# EEG_cap_v2.net
KiCad netlist of a schematic drawn in EAGLE
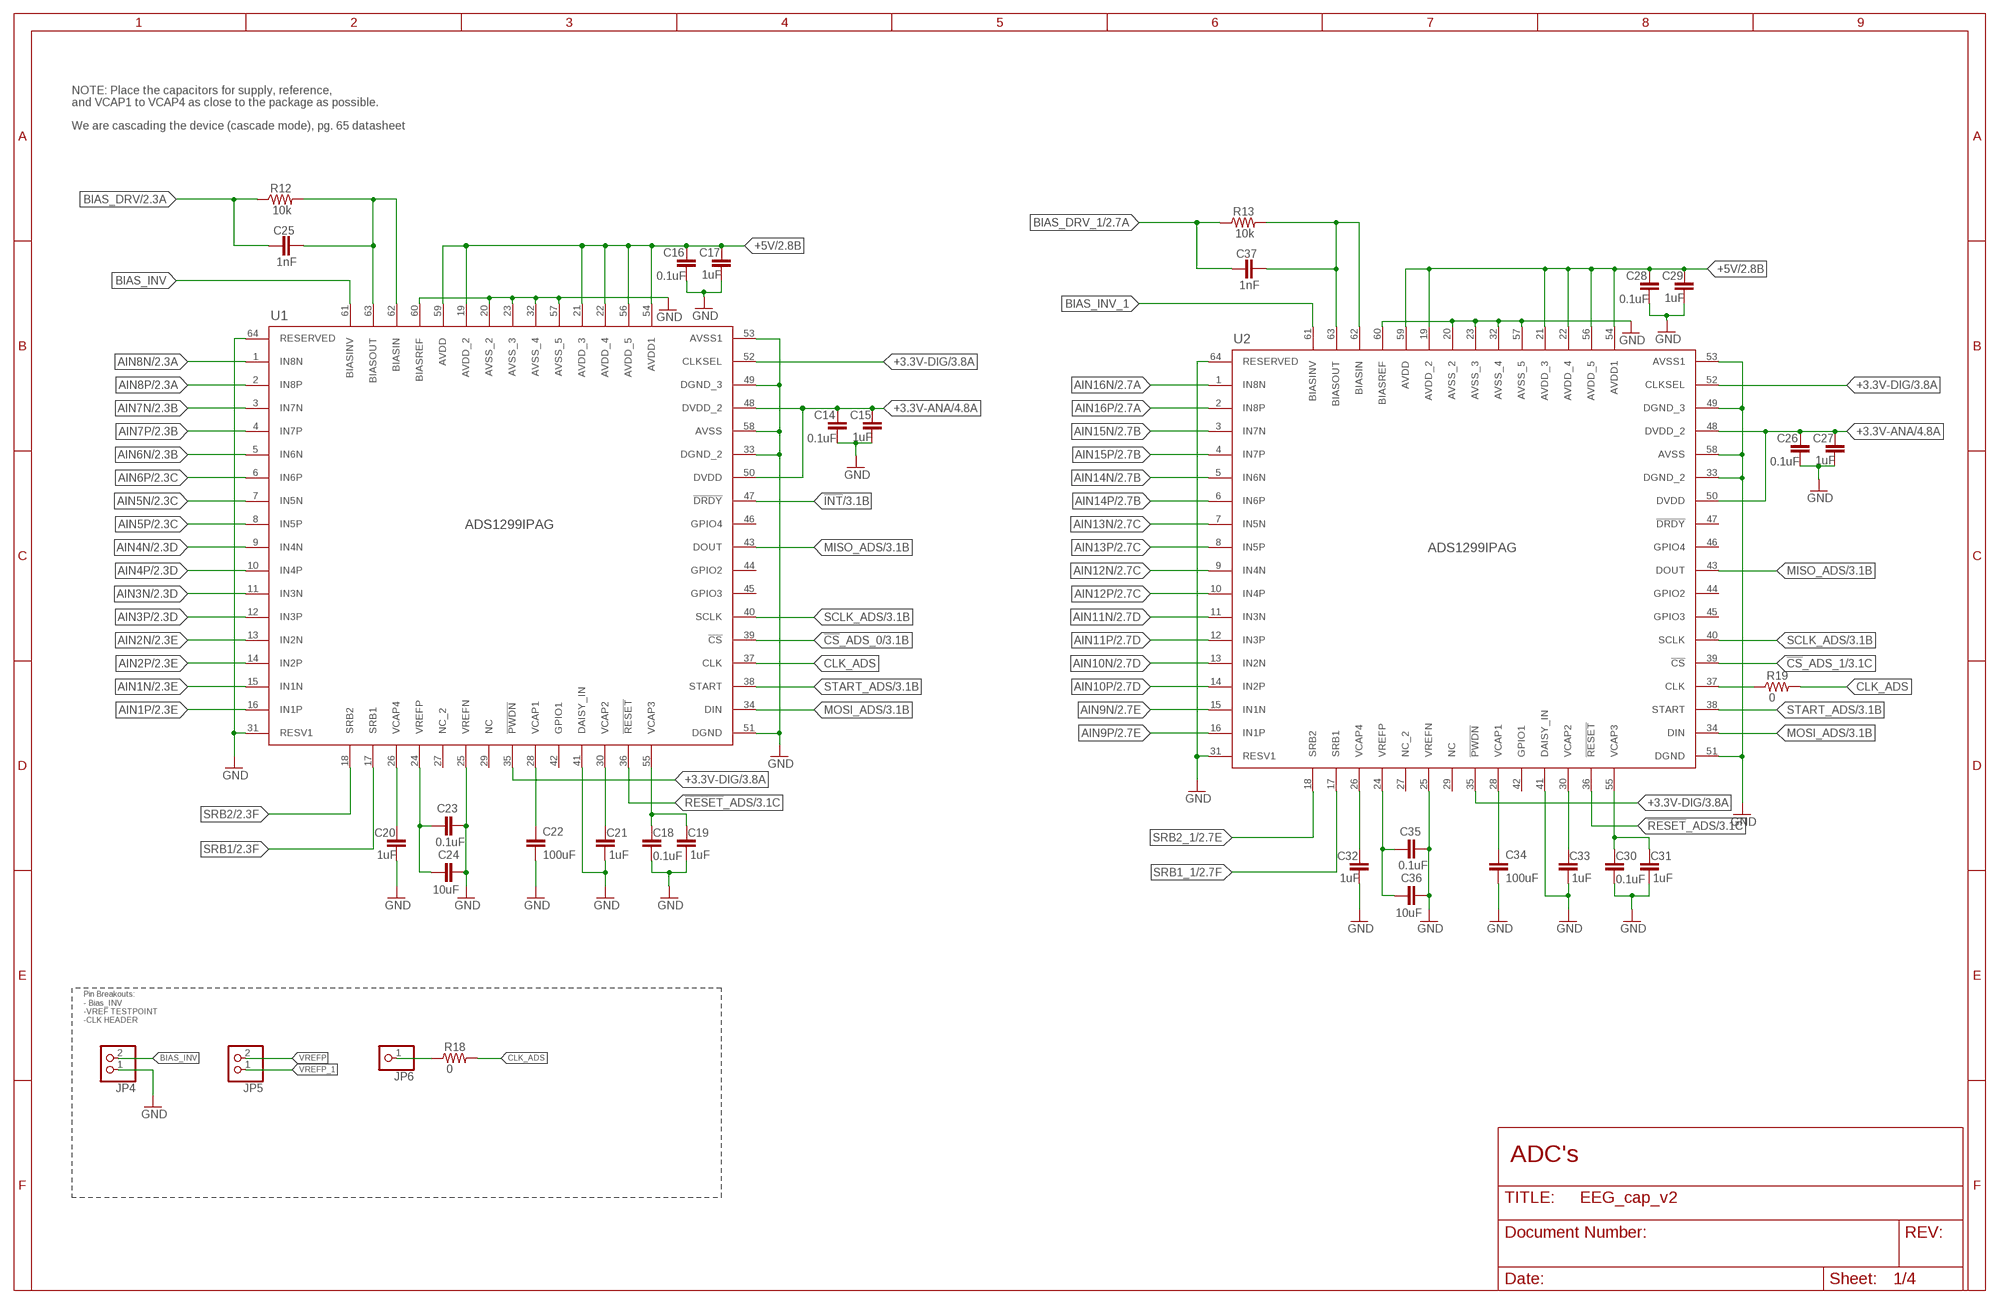
[diagram p0: schematic, sheet 1]
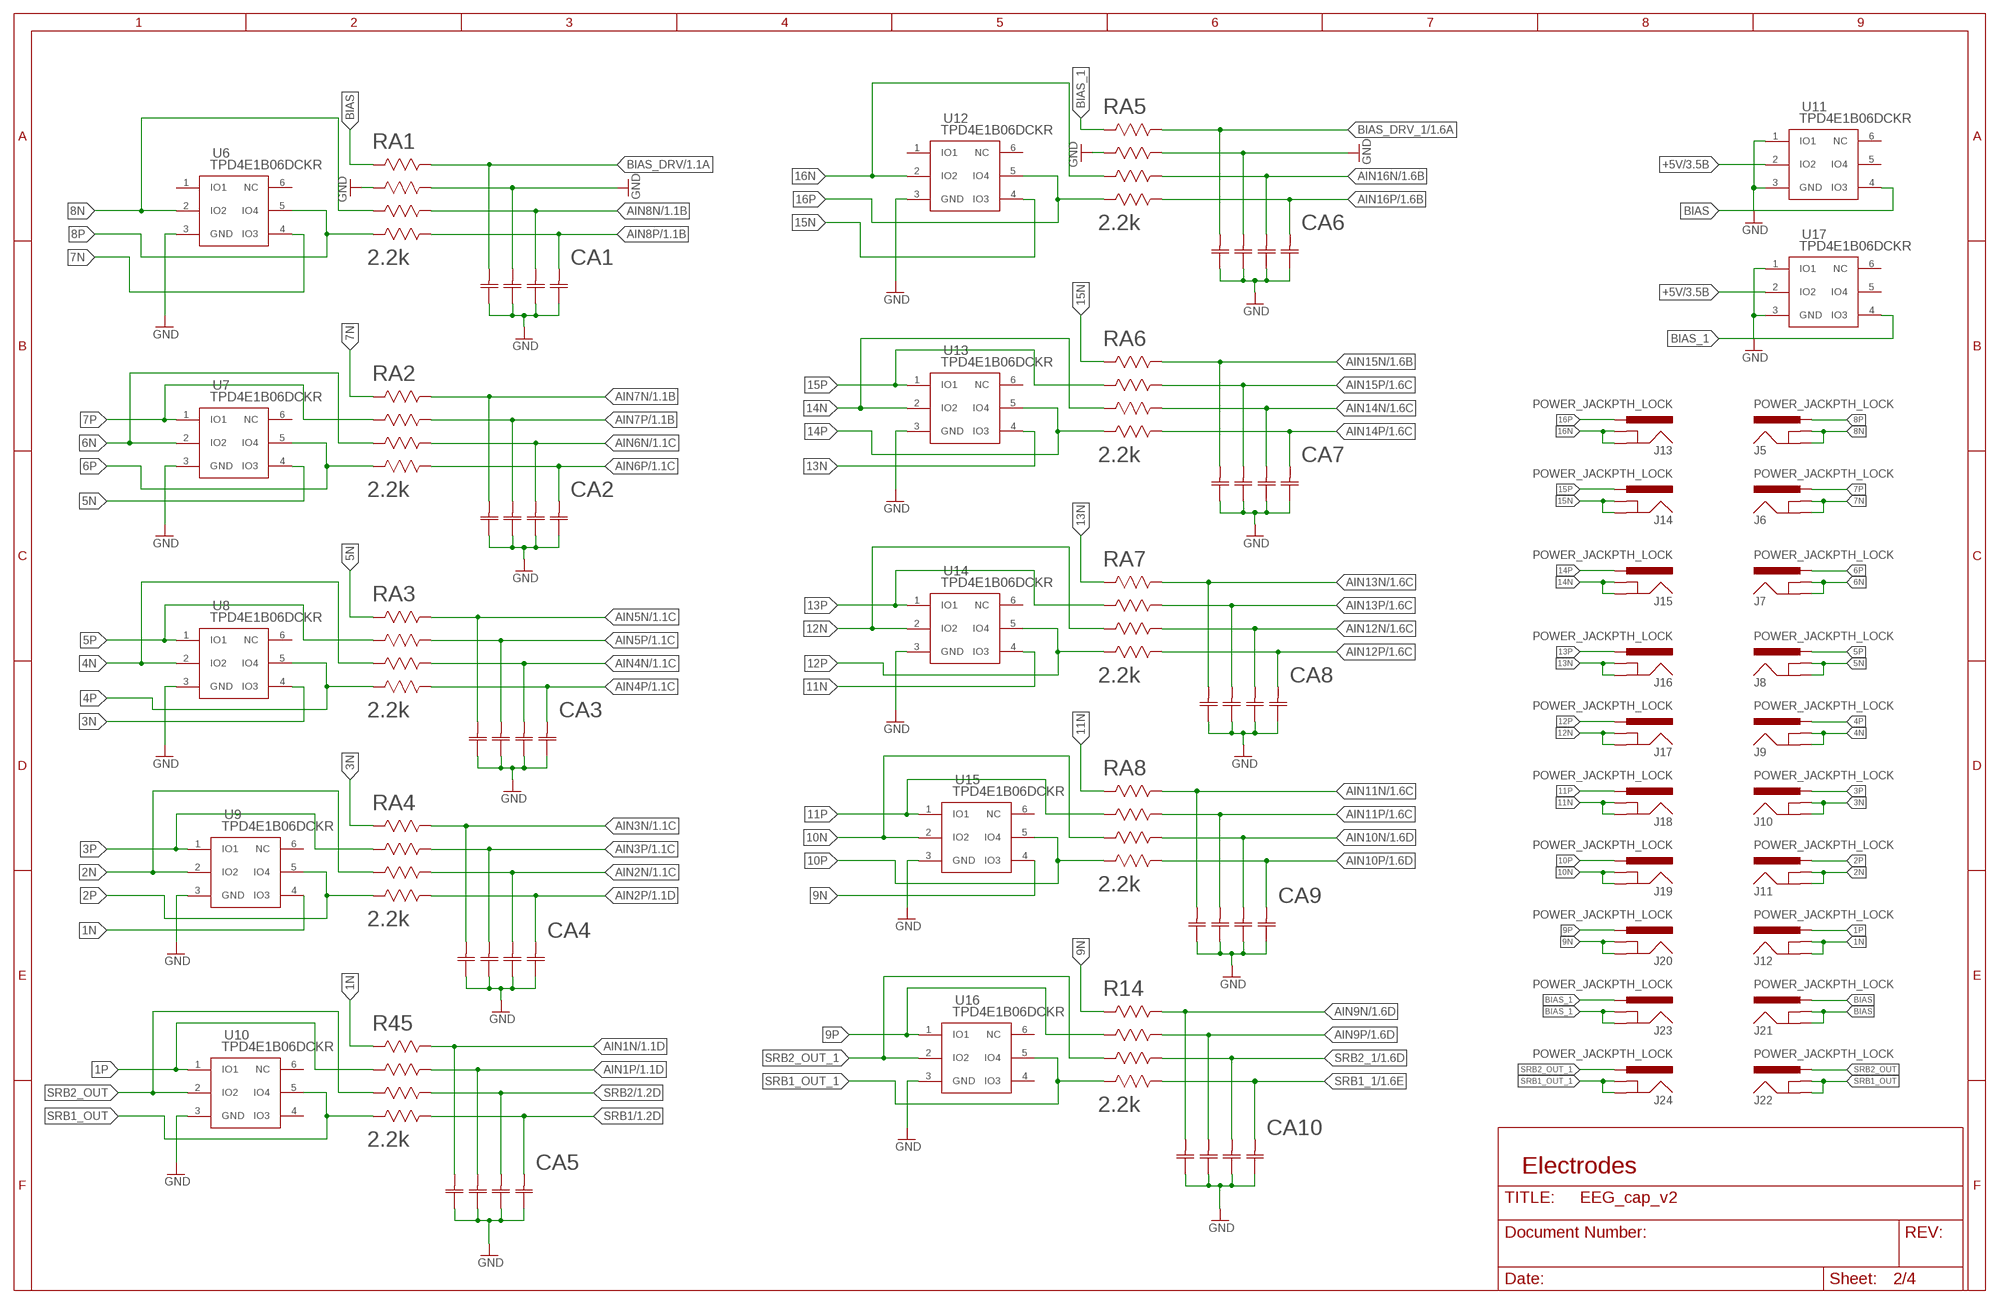
[diagram p1: schematic, sheet 2]
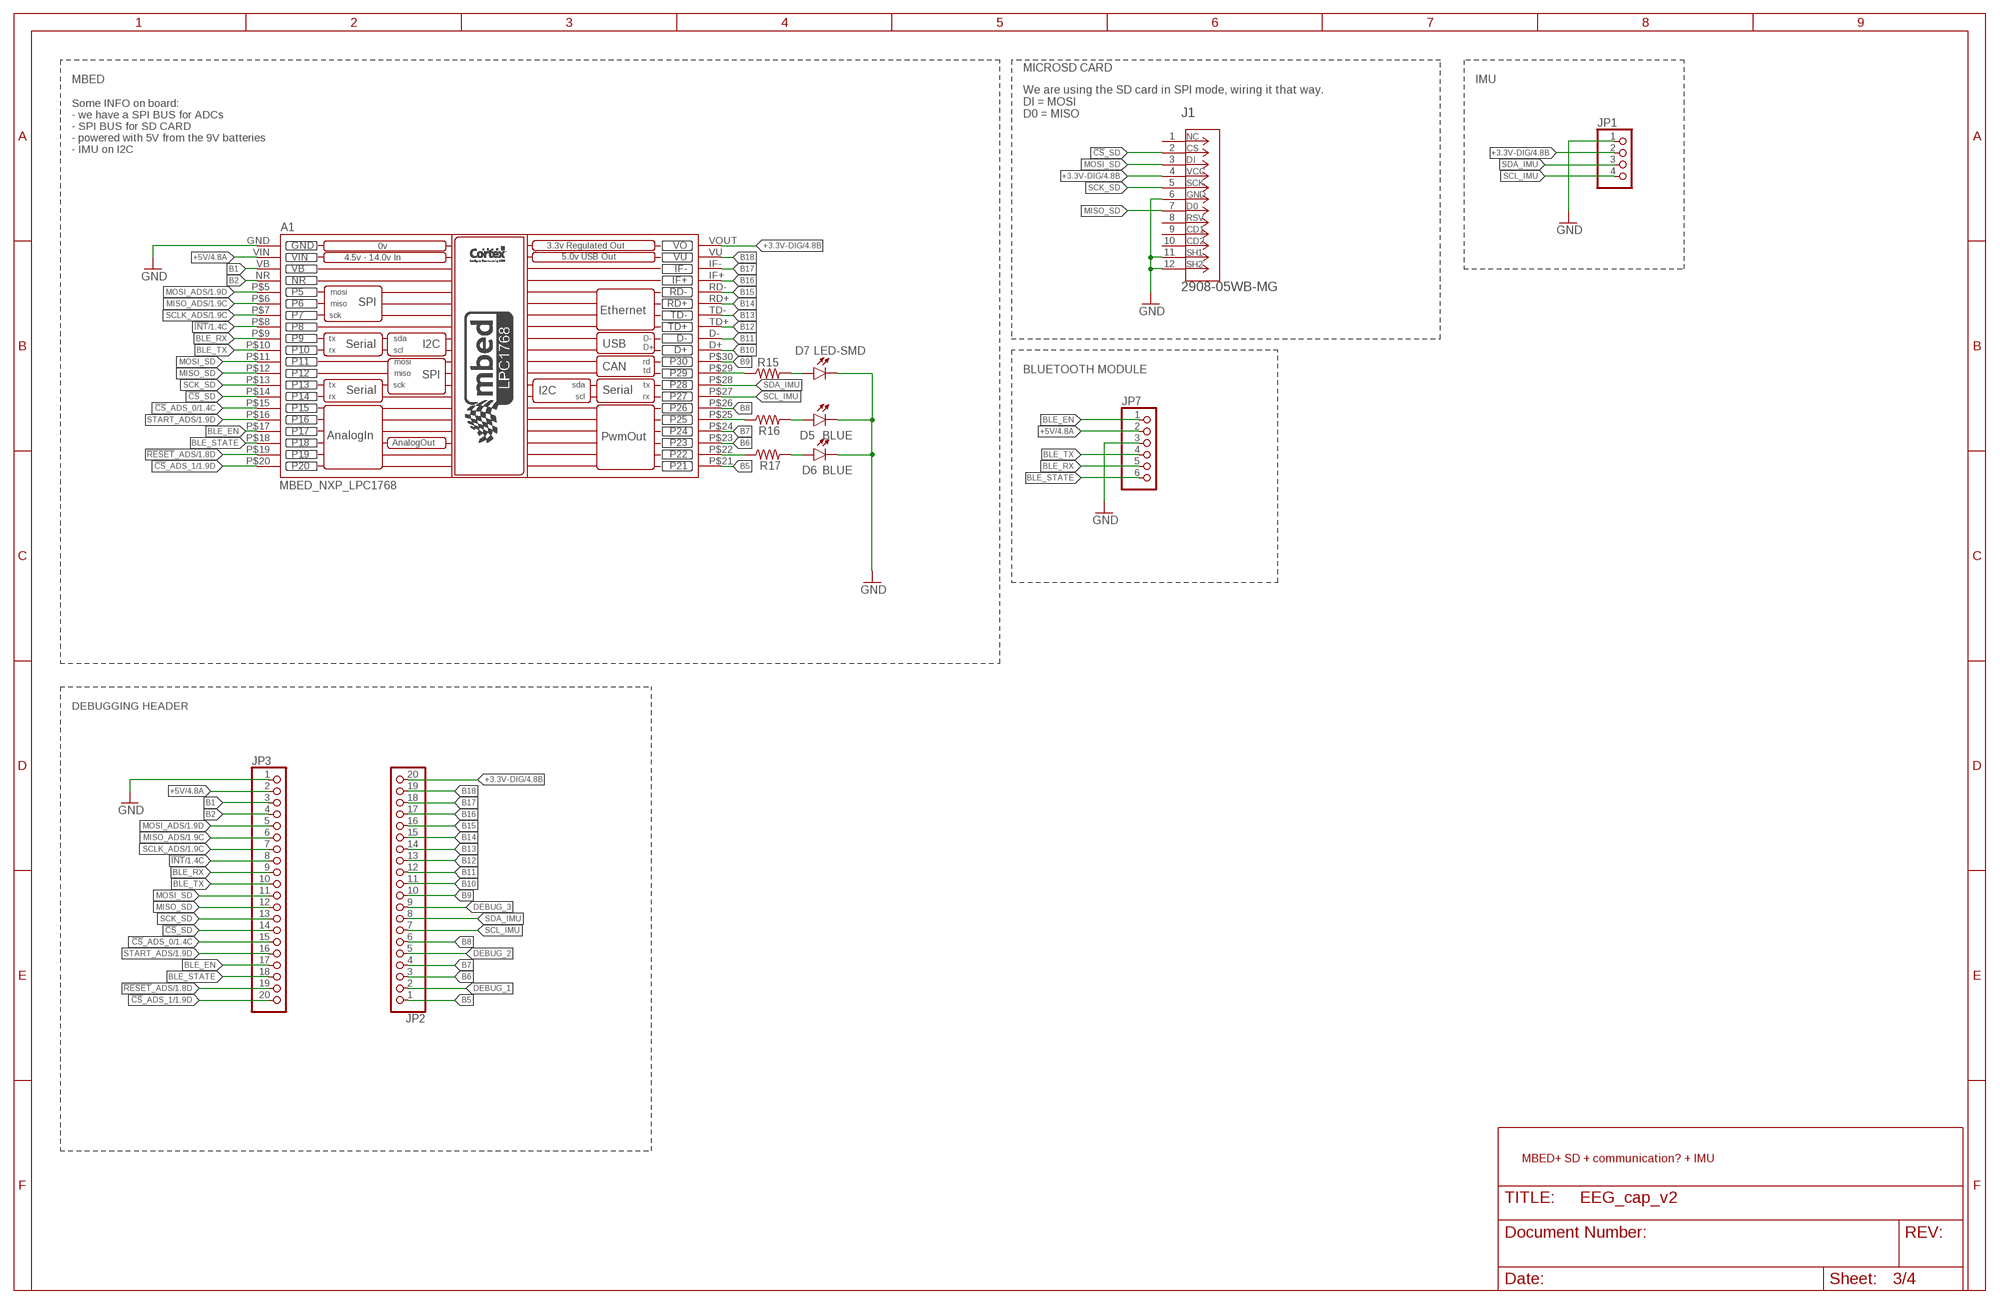
[diagram p2: schematic, sheet 3]
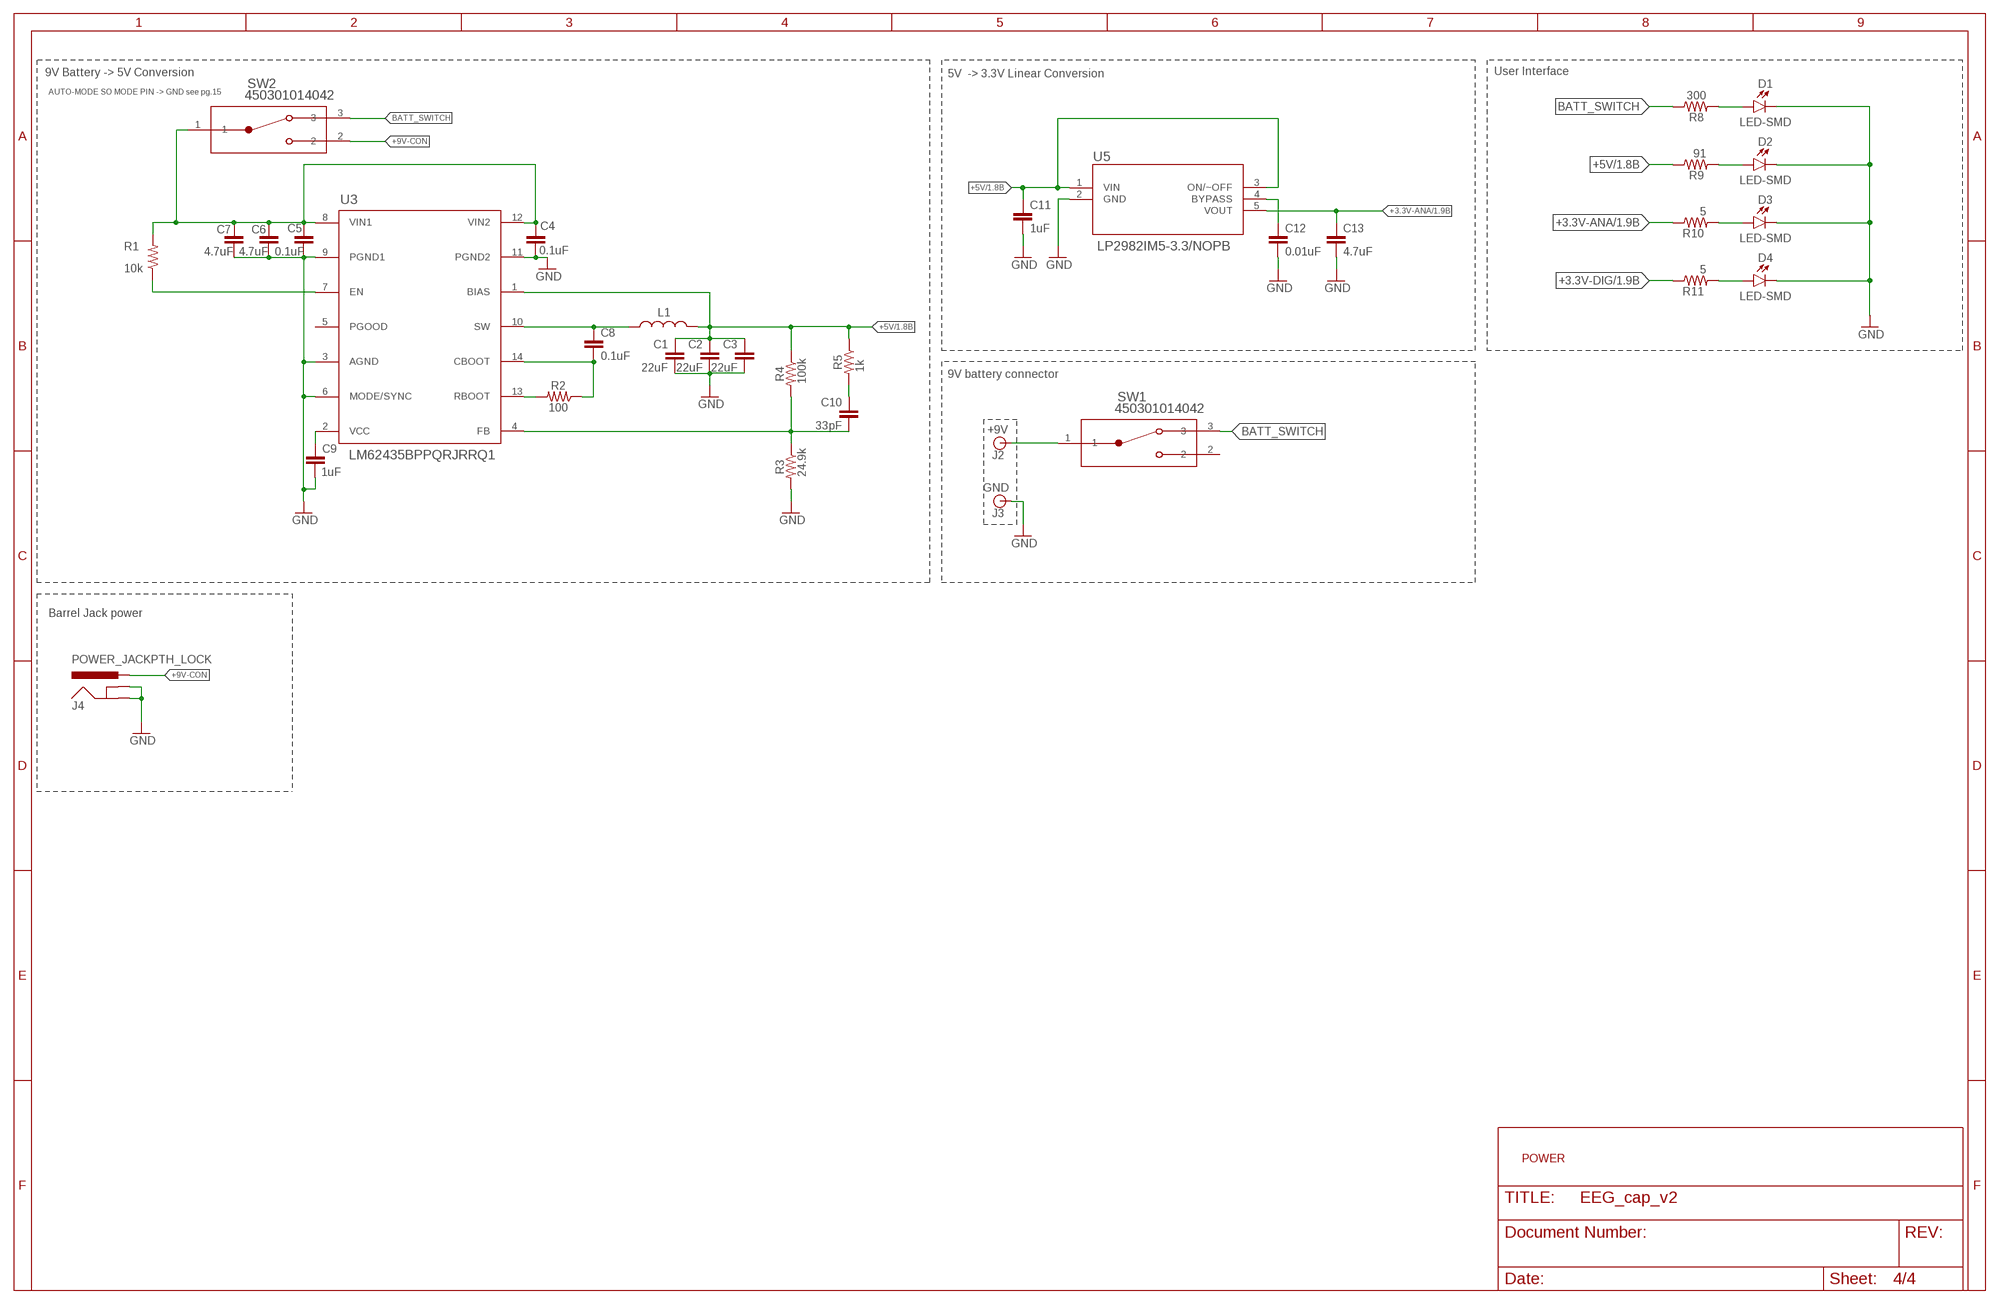
[diagram p3: schematic, sheet 4]

(export (version "E")
  (design (tool "Eeschema 10.0.6"))
  (components
    (comp (ref "C1")
      (value "22uF")
      (footprint "eagle-import:C0805")
      (libsource (lib "eagle-import") (part "C-EUC0805"))
    )
    (comp (ref "C2")
      (value "22uF")
      (footprint "eagle-import:C0805")
      (libsource (lib "eagle-import") (part "C-EUC0805"))
    )
    (comp (ref "C3")
      (value "22uF")
      (footprint "eagle-import:C0805")
      (libsource (lib "eagle-import") (part "C-EUC0805"))
    )
    (comp (ref "C4")
      (value "0.1uF")
      (footprint "eagle-import:C0805")
      (libsource (lib "eagle-import") (part "C-EUC0805"))
    )
    (comp (ref "C5")
      (value "0.1uF")
      (footprint "eagle-import:C0805")
      (libsource (lib "eagle-import") (part "C-EUC0805"))
    )
    (comp (ref "C6")
      (value "4.7uF")
      (footprint "eagle-import:C0805")
      (libsource (lib "eagle-import") (part "C-EUC0805"))
    )
    (comp (ref "C7")
      (value "4.7uF")
      (footprint "eagle-import:C0805")
      (libsource (lib "eagle-import") (part "C-EUC0805"))
    )
    (comp (ref "C8")
      (value "0.1uF")
      (footprint "eagle-import:C0805")
      (libsource (lib "eagle-import") (part "C-EUC0805"))
    )
    (comp (ref "C9")
      (value "1uF")
      (footprint "eagle-import:C0805")
      (libsource (lib "eagle-import") (part "C-EUC0805"))
    )
    (comp (ref "C10")
      (value "33pF")
      (footprint "eagle-import:C0805")
      (libsource (lib "eagle-import") (part "C-EUC0805"))
    )
    (comp (ref "C11")
      (value "1uF")
      (footprint "eagle-import:C0805")
      (libsource (lib "eagle-import") (part "C-EUC0805"))
    )
    (comp (ref "C12")
      (value "0.01uF")
      (footprint "eagle-import:C0805")
      (libsource (lib "eagle-import") (part "C-EUC0805"))
    )
    (comp (ref "C13")
      (value "4.7uF")
      (footprint "eagle-import:C0805")
      (libsource (lib "eagle-import") (part "C-EUC0805"))
    )
    (comp (ref "D1")
      (value "LED-SMD")
      (footprint "eagle-import:LED0603")
      (libsource (lib "eagle-import") (part "LED-SMD"))
    )
    (comp (ref "D2")
      (value "LED-SMD")
      (footprint "eagle-import:LED0603")
      (libsource (lib "eagle-import") (part "LED-SMD"))
    )
    (comp (ref "D3")
      (value "LED-SMD")
      (footprint "eagle-import:LED0603")
      (libsource (lib "eagle-import") (part "LED-SMD"))
    )
    (comp (ref "D4")
      (value "LED-SMD")
      (footprint "eagle-import:LED0603")
      (libsource (lib "eagle-import") (part "LED-SMD"))
    )
    (comp (ref "J2")
      (value "+9V")
      (footprint "eagle-import:BANANA_CONN")
      (libsource (lib "eagle-import") (part "BANANA_CONN"))
    )
    (comp (ref "J3")
      (value "GND")
      (footprint "eagle-import:BANANA_CONN")
      (libsource (lib "eagle-import") (part "BANANA_CONN"))
    )
    (comp (ref "J4")
      (value "POWER_JACKPTH_LOCK")
      (footprint "eagle-import:POWER_JACK_PTH_LOCK")
      (libsource (lib "eagle-import") (part "POWER_JACKPTH_LOCK"))
    )
    (comp (ref "L1")
      (value "DFE252010P-1R5M=P2")
      (footprint "eagle-import:INDC2520X100N")
      (fields (field (name "DIGI-KEY_PART_NUMBER") "490-10636-1-ND") (field (name "MF") "Murata"))
      (libsource (lib "eagle-import") (part "DFE252010P-1R5M=P2"))
    )
    (comp (ref "R1")
      (value "10k")
      (footprint "eagle-import:R0805")
      (libsource (lib "eagle-import") (part "R-US_R0805"))
    )
    (comp (ref "R2")
      (value "100")
      (footprint "eagle-import:R0805")
      (libsource (lib "eagle-import") (part "R-US_R0805"))
    )
    (comp (ref "R3")
      (value "24.9k")
      (footprint "eagle-import:R0805")
      (libsource (lib "eagle-import") (part "R-US_R0805"))
    )
    (comp (ref "R4")
      (value "100k")
      (footprint "eagle-import:R0805")
      (libsource (lib "eagle-import") (part "R-US_R0805"))
    )
    (comp (ref "R5")
      (value "1k")
      (footprint "eagle-import:R0805")
      (libsource (lib "eagle-import") (part "R-US_R0805"))
    )
    (comp (ref "R8")
      (value "300")
      (footprint "eagle-import:R0805")
      (libsource (lib "eagle-import") (part "R-US_R0805"))
    )
    (comp (ref "R9")
      (value "91")
      (footprint "eagle-import:R0805")
      (libsource (lib "eagle-import") (part "R-US_R0805"))
    )
    (comp (ref "R10")
      (value "5")
      (footprint "eagle-import:R0805")
      (libsource (lib "eagle-import") (part "R-US_R0805"))
    )
    (comp (ref "R11")
      (value "5")
      (footprint "eagle-import:R0805")
      (libsource (lib "eagle-import") (part "R-US_R0805"))
    )
    (comp (ref "SW1")
      (value "450301014042")
      (footprint "eagle-import:SW_450301014042_WRE")
      (fields (field (name "COPYRIGHT") "Copyright (C) 2021 Ultra Librarian. All rights reserved."))
      (libsource (lib "eagle-import") (part "450301014042"))
    )
    (comp (ref "SW2")
      (value "450301014042")
      (footprint "eagle-import:SW_450301014042_WRE")
      (fields (field (name "COPYRIGHT") "Copyright (C) 2021 Ultra Librarian. All rights reserved."))
      (libsource (lib "eagle-import") (part "450301014042"))
    )
    (comp (ref "U3")
      (value "LM62435BPPQRJRRQ1")
      (footprint "eagle-import:VQFN-HR14_RJR_TEX")
      (fields (field (name "COPYRIGHT") "Copyright (C) 2021 Ultra Librarian. All rights reserved."))
      (libsource (lib "eagle-import") (part "LM62435BPPQRJRRQ1"))
    )
    (comp (ref "U5")
      (value "LP2982IM5-3.3/NOPB")
      (footprint "eagle-import:MF05A")
      (fields (field (name "COPYRIGHT") "Copyright (C) 2021 Ultra Librarian. All rights reserved."))
      (libsource (lib "eagle-import") (part "LP2982IM5-3.3/NOPB"))
    )
    (comp (ref "C14")
      (value "0.1uF")
      (footprint "eagle-import:C0603")
      (libsource (lib "eagle-import") (part "C-EUC0603"))
    )
    (comp (ref "C15")
      (value "1uF")
      (footprint "eagle-import:C0603")
      (libsource (lib "eagle-import") (part "C-EUC0603"))
    )
    (comp (ref "C16")
      (value "0.1uF")
      (footprint "eagle-import:C0603")
      (libsource (lib "eagle-import") (part "C-EUC0603"))
    )
    (comp (ref "C17")
      (value "1uF")
      (footprint "eagle-import:C0603")
      (libsource (lib "eagle-import") (part "C-EUC0603"))
    )
    (comp (ref "C18")
      (value "0.1uF")
      (footprint "eagle-import:C0603")
      (libsource (lib "eagle-import") (part "C-EUC0603"))
    )
    (comp (ref "C19")
      (value "1uF")
      (footprint "eagle-import:C0603")
      (libsource (lib "eagle-import") (part "C-EUC0603"))
    )
    (comp (ref "C20")
      (value "1uF")
      (footprint "eagle-import:C0603")
      (libsource (lib "eagle-import") (part "C-EUC0603"))
    )
    (comp (ref "C21")
      (value "1uF")
      (footprint "eagle-import:C0603")
      (libsource (lib "eagle-import") (part "C-EUC0603"))
    )
    (comp (ref "C22")
      (value "100uF")
      (footprint "eagle-import:C1210")
      (libsource (lib "eagle-import") (part "C-EUC1210"))
    )
    (comp (ref "C23")
      (value "0.1uF")
      (footprint "eagle-import:C0603")
      (libsource (lib "eagle-import") (part "C-EUC0603"))
    )
    (comp (ref "C24")
      (value "10uF")
      (footprint "eagle-import:C0805")
      (libsource (lib "eagle-import") (part "C-EUC0805"))
    )
    (comp (ref "C25")
      (value "1nF")
      (footprint "eagle-import:C0603")
      (libsource (lib "eagle-import") (part "C-EUC0603"))
    )
    (comp (ref "C26")
      (value "0.1uF")
      (footprint "eagle-import:C0603")
      (libsource (lib "eagle-import") (part "C-EUC0603"))
    )
    (comp (ref "C27")
      (value "1uF")
      (footprint "eagle-import:C0603")
      (libsource (lib "eagle-import") (part "C-EUC0603"))
    )
    (comp (ref "C28")
      (value "0.1uF")
      (footprint "eagle-import:C0603")
      (libsource (lib "eagle-import") (part "C-EUC0603"))
    )
    (comp (ref "C29")
      (value "1uF")
      (footprint "eagle-import:C0603")
      (libsource (lib "eagle-import") (part "C-EUC0603"))
    )
    (comp (ref "C30")
      (value "0.1uF")
      (footprint "eagle-import:C0603")
      (libsource (lib "eagle-import") (part "C-EUC0603"))
    )
    (comp (ref "C31")
      (value "1uF")
      (footprint "eagle-import:C0603")
      (libsource (lib "eagle-import") (part "C-EUC0603"))
    )
    (comp (ref "C32")
      (value "1uF")
      (footprint "eagle-import:C0603")
      (libsource (lib "eagle-import") (part "C-EUC0603"))
    )
    (comp (ref "C33")
      (value "1uF")
      (footprint "eagle-import:C0603")
      (libsource (lib "eagle-import") (part "C-EUC0603"))
    )
    (comp (ref "C34")
      (value "100uF")
      (footprint "eagle-import:C1210")
      (libsource (lib "eagle-import") (part "C-EUC1210"))
    )
    (comp (ref "C35")
      (value "0.1uF")
      (footprint "eagle-import:C0603")
      (libsource (lib "eagle-import") (part "C-EUC0603"))
    )
    (comp (ref "C36")
      (value "10uF")
      (footprint "eagle-import:C0805")
      (libsource (lib "eagle-import") (part "C-EUC0805"))
    )
    (comp (ref "C37")
      (value "1nF")
      (footprint "eagle-import:C0603")
      (libsource (lib "eagle-import") (part "C-EUC0603"))
    )
    (comp (ref "JP4")
      (value "PINHD-1X2")
      (footprint "eagle-import:1X02")
      (libsource (lib "eagle-import") (part "PINHD-1X2"))
    )
    (comp (ref "JP5")
      (value "PINHD-1X2")
      (footprint "eagle-import:1X02")
      (libsource (lib "eagle-import") (part "PINHD-1X2"))
    )
    (comp (ref "JP6")
      (value "PINHD-1X1")
      (footprint "eagle-import:1X01")
      (libsource (lib "eagle-import") (part "PINHD-1X1"))
    )
    (comp (ref "R12")
      (value "10k")
      (footprint "eagle-import:R0805")
      (libsource (lib "eagle-import") (part "R-US_R0805"))
    )
    (comp (ref "R13")
      (value "10k")
      (footprint "eagle-import:R0805")
      (libsource (lib "eagle-import") (part "R-US_R0805"))
    )
    (comp (ref "R18")
      (value "0")
      (footprint "eagle-import:R0805")
      (libsource (lib "eagle-import") (part "R-US_R0805"))
    )
    (comp (ref "R19")
      (value "0")
      (footprint "eagle-import:R0805")
      (libsource (lib "eagle-import") (part "R-US_R0805"))
    )
    (comp (ref "U1")
      (value "ADS1299IPAG")
      (footprint "eagle-import:PAG64_TEX")
      (fields (field (name "COPYRIGHT") "Copyright (C) 2021 Ultra Librarian. All rights reserved."))
      (libsource (lib "eagle-import") (part "ADS1299IPAG"))
    )
    (comp (ref "U2")
      (value "ADS1299IPAG")
      (footprint "eagle-import:PAG64_TEX")
      (fields (field (name "COPYRIGHT") "Copyright (C) 2021 Ultra Librarian. All rights reserved."))
      (libsource (lib "eagle-import") (part "ADS1299IPAG"))
    )
    (comp (ref "A1")
      (value "MBED_NXP_LPC1768")
      (footprint "eagle-import:MBED_LPC1768")
      (libsource (lib "eagle-import") (part "MBED_NXP_LPC1768"))
    )
    (comp (ref "D5")
      (value "BLUE")
      (footprint "eagle-import:LED0603")
      (libsource (lib "eagle-import") (part "LED-SMD"))
    )
    (comp (ref "D6")
      (value "BLUE")
      (footprint "eagle-import:LED0603")
      (libsource (lib "eagle-import") (part "LED-SMD"))
    )
    (comp (ref "D7")
      (value "LED-SMD")
      (footprint "eagle-import:LED0603")
      (libsource (lib "eagle-import") (part "LED-SMD"))
    )
    (comp (ref "J1")
      (value "2908-05WB-MG")
      (footprint "eagle-import:CONN_3M_2900")
      (fields (field (name "COPYRIGHT") "Copyright (C) 2021 Ultra Librarian. All rights reserved."))
      (libsource (lib "eagle-import") (part "2908-05WB-MG"))
    )
    (comp (ref "JP1")
      (value "PINHD-1X4")
      (footprint "eagle-import:1X04")
      (libsource (lib "eagle-import") (part "PINHD-1X4"))
    )
    (comp (ref "JP2")
      (value "PINHD-1X20")
      (footprint "eagle-import:1X20")
      (libsource (lib "eagle-import") (part "PINHD-1X20"))
    )
    (comp (ref "JP3")
      (value "PINHD-1X20")
      (footprint "eagle-import:1X20")
      (libsource (lib "eagle-import") (part "PINHD-1X20"))
    )
    (comp (ref "JP7")
      (value "PINHD-1X6")
      (footprint "eagle-import:1X06")
      (libsource (lib "eagle-import") (part "PINHD-1X6"))
    )
    (comp (ref "R15")
      (value "1K")
      (footprint "eagle-import:R0805")
      (libsource (lib "eagle-import") (part "R-US_R0805"))
    )
    (comp (ref "R16")
      (value "1k")
      (footprint "eagle-import:R0805")
      (libsource (lib "eagle-import") (part "R-US_R0805"))
    )
    (comp (ref "R17")
      (value "1k")
      (footprint "eagle-import:R0805")
      (libsource (lib "eagle-import") (part "R-US_R0805"))
    )
    (comp (ref "CA1")
      (value "CAP_ARRAY")
      (footprint "eagle-import:CAP_CA0612_3P2X1P6_YAG")
      (libsource (lib "eagle-import") (part "CAP_ARRAY"))
    )
    (comp (ref "CA2")
      (value "CAP_ARRAY")
      (footprint "eagle-import:CAP_CA0612_3P2X1P6_YAG")
      (libsource (lib "eagle-import") (part "CAP_ARRAY"))
    )
    (comp (ref "CA3")
      (value "CAP_ARRAY")
      (footprint "eagle-import:CAP_CA0612_3P2X1P6_YAG")
      (libsource (lib "eagle-import") (part "CAP_ARRAY"))
    )
    (comp (ref "CA4")
      (value "CAP_ARRAY")
      (footprint "eagle-import:CAP_CA0612_3P2X1P6_YAG")
      (libsource (lib "eagle-import") (part "CAP_ARRAY"))
    )
    (comp (ref "CA5")
      (value "CAP_ARRAY")
      (footprint "eagle-import:CAP_CA0612_3P2X1P6_YAG")
      (libsource (lib "eagle-import") (part "CAP_ARRAY"))
    )
    (comp (ref "CA6")
      (value "CAP_ARRAY")
      (footprint "eagle-import:CAP_CA0612_3P2X1P6_YAG")
      (libsource (lib "eagle-import") (part "CAP_ARRAY"))
    )
    (comp (ref "CA7")
      (value "CAP_ARRAY")
      (footprint "eagle-import:CAP_CA0612_3P2X1P6_YAG")
      (libsource (lib "eagle-import") (part "CAP_ARRAY"))
    )
    (comp (ref "CA8")
      (value "CAP_ARRAY")
      (footprint "eagle-import:CAP_CA0612_3P2X1P6_YAG")
      (libsource (lib "eagle-import") (part "CAP_ARRAY"))
    )
    (comp (ref "CA9")
      (value "CAP_ARRAY")
      (footprint "eagle-import:CAP_CA0612_3P2X1P6_YAG")
      (libsource (lib "eagle-import") (part "CAP_ARRAY"))
    )
    (comp (ref "CA10")
      (value "CAP_ARRAY")
      (footprint "eagle-import:CAP_CA0612_3P2X1P6_YAG")
      (libsource (lib "eagle-import") (part "CAP_ARRAY"))
    )
    (comp (ref "J5")
      (value "POWER_JACKPTH_LOCK")
      (footprint "eagle-import:POWER_JACK_PTH_LOCK")
      (libsource (lib "eagle-import") (part "POWER_JACKPTH_LOCK"))
    )
    (comp (ref "J6")
      (value "POWER_JACKPTH_LOCK")
      (footprint "eagle-import:POWER_JACK_PTH_LOCK")
      (libsource (lib "eagle-import") (part "POWER_JACKPTH_LOCK"))
    )
    (comp (ref "J7")
      (value "POWER_JACKPTH_LOCK")
      (footprint "eagle-import:POWER_JACK_PTH_LOCK")
      (libsource (lib "eagle-import") (part "POWER_JACKPTH_LOCK"))
    )
    (comp (ref "J8")
      (value "POWER_JACKPTH_LOCK")
      (footprint "eagle-import:POWER_JACK_PTH_LOCK")
      (libsource (lib "eagle-import") (part "POWER_JACKPTH_LOCK"))
    )
    (comp (ref "J9")
      (value "POWER_JACKPTH_LOCK")
      (footprint "eagle-import:POWER_JACK_PTH_LOCK")
      (libsource (lib "eagle-import") (part "POWER_JACKPTH_LOCK"))
    )
    (comp (ref "J10")
      (value "POWER_JACKPTH_LOCK")
      (footprint "eagle-import:POWER_JACK_PTH_LOCK")
      (libsource (lib "eagle-import") (part "POWER_JACKPTH_LOCK"))
    )
    (comp (ref "J11")
      (value "POWER_JACKPTH_LOCK")
      (footprint "eagle-import:POWER_JACK_PTH_LOCK")
      (libsource (lib "eagle-import") (part "POWER_JACKPTH_LOCK"))
    )
    (comp (ref "J12")
      (value "POWER_JACKPTH_LOCK")
      (footprint "eagle-import:POWER_JACK_PTH_LOCK")
      (libsource (lib "eagle-import") (part "POWER_JACKPTH_LOCK"))
    )
    (comp (ref "J13")
      (value "POWER_JACKPTH_LOCK")
      (footprint "eagle-import:POWER_JACK_PTH_LOCK")
      (libsource (lib "eagle-import") (part "POWER_JACKPTH_LOCK"))
    )
    (comp (ref "J14")
      (value "POWER_JACKPTH_LOCK")
      (footprint "eagle-import:POWER_JACK_PTH_LOCK")
      (libsource (lib "eagle-import") (part "POWER_JACKPTH_LOCK"))
    )
    (comp (ref "J15")
      (value "POWER_JACKPTH_LOCK")
      (footprint "eagle-import:POWER_JACK_PTH_LOCK")
      (libsource (lib "eagle-import") (part "POWER_JACKPTH_LOCK"))
    )
    (comp (ref "J16")
      (value "POWER_JACKPTH_LOCK")
      (footprint "eagle-import:POWER_JACK_PTH_LOCK")
      (libsource (lib "eagle-import") (part "POWER_JACKPTH_LOCK"))
    )
    (comp (ref "J17")
      (value "POWER_JACKPTH_LOCK")
      (footprint "eagle-import:POWER_JACK_PTH_LOCK")
      (libsource (lib "eagle-import") (part "POWER_JACKPTH_LOCK"))
    )
    (comp (ref "J18")
      (value "POWER_JACKPTH_LOCK")
      (footprint "eagle-import:POWER_JACK_PTH_LOCK")
      (libsource (lib "eagle-import") (part "POWER_JACKPTH_LOCK"))
    )
    (comp (ref "J19")
      (value "POWER_JACKPTH_LOCK")
      (footprint "eagle-import:POWER_JACK_PTH_LOCK")
      (libsource (lib "eagle-import") (part "POWER_JACKPTH_LOCK"))
    )
    (comp (ref "J20")
      (value "POWER_JACKPTH_LOCK")
      (footprint "eagle-import:POWER_JACK_PTH_LOCK")
      (libsource (lib "eagle-import") (part "POWER_JACKPTH_LOCK"))
    )
    (comp (ref "J21")
      (value "POWER_JACKPTH_LOCK")
      (footprint "eagle-import:POWER_JACK_PTH_LOCK")
      (libsource (lib "eagle-import") (part "POWER_JACKPTH_LOCK"))
    )
    (comp (ref "J22")
      (value "POWER_JACKPTH_LOCK")
      (footprint "eagle-import:POWER_JACK_PTH_LOCK")
      (libsource (lib "eagle-import") (part "POWER_JACKPTH_LOCK"))
    )
    (comp (ref "J23")
      (value "POWER_JACKPTH_LOCK")
      (footprint "eagle-import:POWER_JACK_PTH_LOCK")
      (libsource (lib "eagle-import") (part "POWER_JACKPTH_LOCK"))
    )
    (comp (ref "J24")
      (value "POWER_JACKPTH_LOCK")
      (footprint "eagle-import:POWER_JACK_PTH_LOCK")
      (libsource (lib "eagle-import") (part "POWER_JACKPTH_LOCK"))
    )
    (comp (ref "R14")
      (value "2.2k")
      (footprint "eagle-import:BO_CAT16")
      (fields
        (field (name "MANUFACTURER_PART_NUMBER") "CAT16-220J4LF")
        (field (name "COPYRIGHT") "Copyright (C) 2021 Ultra Librarian. All rights reserved.")
      )
      (libsource (lib "eagle-import") (part "CAT16-220J4LF"))
    )
    (comp (ref "R45")
      (value "2.2k")
      (footprint "eagle-import:BO_CAT16")
      (fields
        (field (name "MANUFACTURER_PART_NUMBER") "CAT16-220J4LF")
        (field (name "COPYRIGHT") "Copyright (C) 2021 Ultra Librarian. All rights reserved.")
      )
      (libsource (lib "eagle-import") (part "CAT16-220J4LF"))
    )
    (comp (ref "RA1")
      (value "2.2k")
      (footprint "eagle-import:BO_CAT16")
      (fields
        (field (name "MANUFACTURER_PART_NUMBER") "CAT16-220J4LF")
        (field (name "COPYRIGHT") "Copyright (C) 2021 Ultra Librarian. All rights reserved.")
      )
      (libsource (lib "eagle-import") (part "CAT16-220J4LF"))
    )
    (comp (ref "RA2")
      (value "2.2k")
      (footprint "eagle-import:BO_CAT16")
      (fields
        (field (name "MANUFACTURER_PART_NUMBER") "CAT16-220J4LF")
        (field (name "COPYRIGHT") "Copyright (C) 2021 Ultra Librarian. All rights reserved.")
      )
      (libsource (lib "eagle-import") (part "CAT16-220J4LF"))
    )
    (comp (ref "RA3")
      (value "2.2k")
      (footprint "eagle-import:BO_CAT16")
      (fields
        (field (name "MANUFACTURER_PART_NUMBER") "CAT16-220J4LF")
        (field (name "COPYRIGHT") "Copyright (C) 2021 Ultra Librarian. All rights reserved.")
      )
      (libsource (lib "eagle-import") (part "CAT16-220J4LF"))
    )
    (comp (ref "RA4")
      (value "2.2k")
      (footprint "eagle-import:BO_CAT16")
      (fields
        (field (name "MANUFACTURER_PART_NUMBER") "CAT16-220J4LF")
        (field (name "COPYRIGHT") "Copyright (C) 2021 Ultra Librarian. All rights reserved.")
      )
      (libsource (lib "eagle-import") (part "CAT16-220J4LF"))
    )
    (comp (ref "RA5")
      (value "2.2k")
      (footprint "eagle-import:BO_CAT16")
      (fields
        (field (name "MANUFACTURER_PART_NUMBER") "CAT16-220J4LF")
        (field (name "COPYRIGHT") "Copyright (C) 2021 Ultra Librarian. All rights reserved.")
      )
      (libsource (lib "eagle-import") (part "CAT16-220J4LF"))
    )
    (comp (ref "RA6")
      (value "2.2k")
      (footprint "eagle-import:BO_CAT16")
      (fields
        (field (name "MANUFACTURER_PART_NUMBER") "CAT16-220J4LF")
        (field (name "COPYRIGHT") "Copyright (C) 2021 Ultra Librarian. All rights reserved.")
      )
      (libsource (lib "eagle-import") (part "CAT16-220J4LF"))
    )
    (comp (ref "RA7")
      (value "2.2k")
      (footprint "eagle-import:BO_CAT16")
      (fields
        (field (name "MANUFACTURER_PART_NUMBER") "CAT16-220J4LF")
        (field (name "COPYRIGHT") "Copyright (C) 2021 Ultra Librarian. All rights reserved.")
      )
      (libsource (lib "eagle-import") (part "CAT16-220J4LF"))
    )
    (comp (ref "RA8")
      (value "2.2k")
      (footprint "eagle-import:BO_CAT16")
      (fields
        (field (name "MANUFACTURER_PART_NUMBER") "CAT16-220J4LF")
        (field (name "COPYRIGHT") "Copyright (C) 2021 Ultra Librarian. All rights reserved.")
      )
      (libsource (lib "eagle-import") (part "CAT16-220J4LF"))
    )
    (comp (ref "U6")
      (value "TPD4E1B06DCKR")
      (footprint "eagle-import:DCK6_TEX")
      (fields (field (name "COPYRIGHT") "Copyright (C) 2021 Ultra Librarian. All rights reserved."))
      (libsource (lib "eagle-import") (part "TPD4E1B06DCKR"))
    )
    (comp (ref "U7")
      (value "TPD4E1B06DCKR")
      (footprint "eagle-import:DCK6_TEX")
      (fields (field (name "COPYRIGHT") "Copyright (C) 2021 Ultra Librarian. All rights reserved."))
      (libsource (lib "eagle-import") (part "TPD4E1B06DCKR"))
    )
    (comp (ref "U8")
      (value "TPD4E1B06DCKR")
      (footprint "eagle-import:DCK6_TEX")
      (fields (field (name "COPYRIGHT") "Copyright (C) 2021 Ultra Librarian. All rights reserved."))
      (libsource (lib "eagle-import") (part "TPD4E1B06DCKR"))
    )
    (comp (ref "U9")
      (value "TPD4E1B06DCKR")
      (footprint "eagle-import:DCK6_TEX")
      (fields (field (name "COPYRIGHT") "Copyright (C) 2021 Ultra Librarian. All rights reserved."))
      (libsource (lib "eagle-import") (part "TPD4E1B06DCKR"))
    )
    (comp (ref "U10")
      (value "TPD4E1B06DCKR")
      (footprint "eagle-import:DCK6_TEX")
      (fields (field (name "COPYRIGHT") "Copyright (C) 2021 Ultra Librarian. All rights reserved."))
      (libsource (lib "eagle-import") (part "TPD4E1B06DCKR"))
    )
    (comp (ref "U11")
      (value "TPD4E1B06DCKR")
      (footprint "eagle-import:DCK6_TEX")
      (fields (field (name "COPYRIGHT") "Copyright (C) 2021 Ultra Librarian. All rights reserved."))
      (libsource (lib "eagle-import") (part "TPD4E1B06DCKR"))
    )
    (comp (ref "U12")
      (value "TPD4E1B06DCKR")
      (footprint "eagle-import:DCK6_TEX")
      (fields (field (name "COPYRIGHT") "Copyright (C) 2021 Ultra Librarian. All rights reserved."))
      (libsource (lib "eagle-import") (part "TPD4E1B06DCKR"))
    )
    (comp (ref "U13")
      (value "TPD4E1B06DCKR")
      (footprint "eagle-import:DCK6_TEX")
      (fields (field (name "COPYRIGHT") "Copyright (C) 2021 Ultra Librarian. All rights reserved."))
      (libsource (lib "eagle-import") (part "TPD4E1B06DCKR"))
    )
    (comp (ref "U14")
      (value "TPD4E1B06DCKR")
      (footprint "eagle-import:DCK6_TEX")
      (fields (field (name "COPYRIGHT") "Copyright (C) 2021 Ultra Librarian. All rights reserved."))
      (libsource (lib "eagle-import") (part "TPD4E1B06DCKR"))
    )
    (comp (ref "U15")
      (value "TPD4E1B06DCKR")
      (footprint "eagle-import:DCK6_TEX")
      (fields (field (name "COPYRIGHT") "Copyright (C) 2021 Ultra Librarian. All rights reserved."))
      (libsource (lib "eagle-import") (part "TPD4E1B06DCKR"))
    )
    (comp (ref "U16")
      (value "TPD4E1B06DCKR")
      (footprint "eagle-import:DCK6_TEX")
      (fields (field (name "COPYRIGHT") "Copyright (C) 2021 Ultra Librarian. All rights reserved."))
      (libsource (lib "eagle-import") (part "TPD4E1B06DCKR"))
    )
    (comp (ref "U17")
      (value "TPD4E1B06DCKR")
      (footprint "eagle-import:DCK6_TEX")
      (fields (field (name "COPYRIGHT") "Copyright (C) 2021 Ultra Librarian. All rights reserved."))
      (libsource (lib "eagle-import") (part "TPD4E1B06DCKR"))
    )
  )
  (nets
    (net (code "1") (name "+3.3V-ANA") (class "Default")
      (node (ref "C13") (pin "1") (pinfunction "1_1") (pintype "passive"))
      (node (ref "C14") (pin "1") (pinfunction "1_1") (pintype "passive"))
      (node (ref "C15") (pin "1") (pinfunction "1_1") (pintype "passive"))
      (node (ref "C26") (pin "1") (pinfunction "1_1") (pintype "passive"))
      (node (ref "C27") (pin "1") (pinfunction "1_1") (pintype "passive"))
      (node (ref "R10") (pin "1") (pinfunction "1_1") (pintype "passive"))
      (node (ref "U1") (pin "48") (pinfunction "DVDD_2_48") (pintype "power_in"))
      (node (ref "U1") (pin "50") (pinfunction "DVDD_50") (pintype "power_in"))
      (node (ref "U2") (pin "48") (pinfunction "DVDD_2_48") (pintype "power_in"))
      (node (ref "U2") (pin "50") (pinfunction "DVDD_50") (pintype "power_in"))
      (node (ref "U5") (pin "5") (pinfunction "VOUT_5") (pintype "output"))
    )
    (net (code "2") (name "+3.3V-DIG") (class "Default")
      (node (ref "A1") (pin "VOUT") (pinfunction "VO_VOUT") (pintype "passive"))
      (node (ref "J1") (pin "4") (pinfunction "4_4") (pintype "passive"))
      (node (ref "JP1") (pin "2") (pinfunction "2_2") (pintype "passive"))
      (node (ref "JP2") (pin "20") (pinfunction "20_20") (pintype "passive"))
      (node (ref "R11") (pin "1") (pinfunction "1_1") (pintype "passive"))
      (node (ref "U1") (pin "35") (pinfunction "~{PWDN}_35") (pintype "power_in"))
      (node (ref "U1") (pin "52") (pinfunction "CLKSEL_52") (pintype "input"))
      (node (ref "U2") (pin "35") (pinfunction "~{PWDN}_35") (pintype "power_in"))
      (node (ref "U2") (pin "52") (pinfunction "CLKSEL_52") (pintype "input"))
    )
    (net (code "3") (name "+5V") (class "Default")
      (node (ref "A1") (pin "VIN") (pinfunction "VIN_VIN") (pintype "passive"))
      (node (ref "C1") (pin "1") (pinfunction "1_1") (pintype "passive"))
      (node (ref "C11") (pin "1") (pinfunction "1_1") (pintype "passive"))
      (node (ref "C16") (pin "1") (pinfunction "1_1") (pintype "passive"))
      (node (ref "C17") (pin "1") (pinfunction "1_1") (pintype "passive"))
      (node (ref "C2") (pin "1") (pinfunction "1_1") (pintype "passive"))
      (node (ref "C28") (pin "1") (pinfunction "1_1") (pintype "passive"))
      (node (ref "C29") (pin "1") (pinfunction "1_1") (pintype "passive"))
      (node (ref "C3") (pin "1") (pinfunction "1_1") (pintype "passive"))
      (node (ref "JP3") (pin "2") (pinfunction "2_2") (pintype "passive"))
      (node (ref "JP7") (pin "2") (pinfunction "2_2") (pintype "passive"))
      (node (ref "L1") (pin "2") (pinfunction "2_2") (pintype "passive"))
      (node (ref "R4") (pin "1") (pinfunction "1_1") (pintype "passive"))
      (node (ref "R5") (pin "1") (pinfunction "1_1") (pintype "passive"))
      (node (ref "R9") (pin "1") (pinfunction "1_1") (pintype "passive"))
      (node (ref "U1") (pin "19") (pinfunction "AVDD_2_19") (pintype "power_in"))
      (node (ref "U1") (pin "21") (pinfunction "AVDD_3_21") (pintype "power_in"))
      (node (ref "U1") (pin "22") (pinfunction "AVDD_4_22") (pintype "power_in"))
      (node (ref "U1") (pin "54") (pinfunction "AVDD1_54") (pintype "power_in"))
      (node (ref "U1") (pin "56") (pinfunction "AVDD_5_56") (pintype "power_in"))
      (node (ref "U1") (pin "59") (pinfunction "AVDD_59") (pintype "power_in"))
      (node (ref "U11") (pin "2") (pinfunction "IO2_2") (pintype "bidirectional"))
      (node (ref "U17") (pin "2") (pinfunction "IO2_2") (pintype "bidirectional"))
      (node (ref "U2") (pin "19") (pinfunction "AVDD_2_19") (pintype "power_in"))
      (node (ref "U2") (pin "21") (pinfunction "AVDD_3_21") (pintype "power_in"))
      (node (ref "U2") (pin "22") (pinfunction "AVDD_4_22") (pintype "power_in"))
      (node (ref "U2") (pin "54") (pinfunction "AVDD1_54") (pintype "power_in"))
      (node (ref "U2") (pin "56") (pinfunction "AVDD_5_56") (pintype "power_in"))
      (node (ref "U2") (pin "59") (pinfunction "AVDD_59") (pintype "power_in"))
      (node (ref "U3") (pin "1") (pinfunction "BIAS_1") (pintype "passive"))
      (node (ref "U5") (pin "1") (pinfunction "VIN_1") (pintype "input"))
      (node (ref "U5") (pin "3") (pinfunction "ON/~{OFF}_3") (pintype "passive"))
    )
    (net (code "4") (name "+9V-CON") (class "Default")
      (node (ref "J4") (pin "PWR") (pinfunction "PWR_PWR") (pintype "bidirectional"))
      (node (ref "SW2") (pin "2") (pinfunction "2_2") (pintype "passive"))
    )
    (net (code "5") (name "1N") (class "Default")
      (node (ref "J12") (pin "GND") (pinfunction "GND_GND") (pintype "bidirectional"))
      (node (ref "J12") (pin "GNDBREAK") (pinfunction "GNDBREAK_GNDBREAK") (pintype "bidirectional"))
      (node (ref "R45") (pin "1") (pinfunction "1_1") (pintype "passive"))
      (node (ref "U9") (pin "4") (pinfunction "IO3_4") (pintype "bidirectional"))
    )
    (net (code "6") (name "1P") (class "Default")
      (node (ref "J12") (pin "PWR") (pinfunction "PWR_PWR") (pintype "bidirectional"))
      (node (ref "R45") (pin "2") (pinfunction "2_2") (pintype "passive"))
      (node (ref "U10") (pin "1") (pinfunction "IO1_1") (pintype "bidirectional"))
    )
    (net (code "7") (name "2N") (class "Default")
      (node (ref "J11") (pin "GND") (pinfunction "GND_GND") (pintype "bidirectional"))
      (node (ref "J11") (pin "GNDBREAK") (pinfunction "GNDBREAK_GNDBREAK") (pintype "bidirectional"))
      (node (ref "RA4") (pin "3") (pinfunction "3_3") (pintype "passive"))
      (node (ref "U9") (pin "2") (pinfunction "IO2_2") (pintype "bidirectional"))
    )
    (net (code "8") (name "2P") (class "Default")
      (node (ref "J11") (pin "PWR") (pinfunction "PWR_PWR") (pintype "bidirectional"))
      (node (ref "RA4") (pin "4") (pinfunction "4_4") (pintype "passive"))
      (node (ref "U9") (pin "5") (pinfunction "IO4_5") (pintype "bidirectional"))
    )
    (net (code "9") (name "3N") (class "Default")
      (node (ref "J10") (pin "GND") (pinfunction "GND_GND") (pintype "bidirectional"))
      (node (ref "J10") (pin "GNDBREAK") (pinfunction "GNDBREAK_GNDBREAK") (pintype "bidirectional"))
      (node (ref "RA4") (pin "1") (pinfunction "1_1") (pintype "passive"))
      (node (ref "U8") (pin "4") (pinfunction "IO3_4") (pintype "bidirectional"))
    )
    (net (code "10") (name "3P") (class "Default")
      (node (ref "J10") (pin "PWR") (pinfunction "PWR_PWR") (pintype "bidirectional"))
      (node (ref "RA4") (pin "2") (pinfunction "2_2") (pintype "passive"))
      (node (ref "U9") (pin "1") (pinfunction "IO1_1") (pintype "bidirectional"))
    )
    (net (code "11") (name "4N") (class "Default")
      (node (ref "J9") (pin "GND") (pinfunction "GND_GND") (pintype "bidirectional"))
      (node (ref "J9") (pin "GNDBREAK") (pinfunction "GNDBREAK_GNDBREAK") (pintype "bidirectional"))
      (node (ref "RA3") (pin "3") (pinfunction "3_3") (pintype "passive"))
      (node (ref "U8") (pin "2") (pinfunction "IO2_2") (pintype "bidirectional"))
    )
    (net (code "12") (name "4P") (class "Default")
      (node (ref "J9") (pin "PWR") (pinfunction "PWR_PWR") (pintype "bidirectional"))
      (node (ref "RA3") (pin "4") (pinfunction "4_4") (pintype "passive"))
      (node (ref "U8") (pin "5") (pinfunction "IO4_5") (pintype "bidirectional"))
    )
    (net (code "13") (name "5N") (class "Default")
      (node (ref "J8") (pin "GND") (pinfunction "GND_GND") (pintype "bidirectional"))
      (node (ref "J8") (pin "GNDBREAK") (pinfunction "GNDBREAK_GNDBREAK") (pintype "bidirectional"))
      (node (ref "RA3") (pin "1") (pinfunction "1_1") (pintype "passive"))
      (node (ref "U7") (pin "4") (pinfunction "IO3_4") (pintype "bidirectional"))
    )
    (net (code "14") (name "5P") (class "Default")
      (node (ref "J8") (pin "PWR") (pinfunction "PWR_PWR") (pintype "bidirectional"))
      (node (ref "RA3") (pin "2") (pinfunction "2_2") (pintype "passive"))
      (node (ref "U8") (pin "1") (pinfunction "IO1_1") (pintype "bidirectional"))
    )
    (net (code "15") (name "6N") (class "Default")
      (node (ref "J7") (pin "GND") (pinfunction "GND_GND") (pintype "bidirectional"))
      (node (ref "J7") (pin "GNDBREAK") (pinfunction "GNDBREAK_GNDBREAK") (pintype "bidirectional"))
      (node (ref "RA2") (pin "3") (pinfunction "3_3") (pintype "passive"))
      (node (ref "U7") (pin "2") (pinfunction "IO2_2") (pintype "bidirectional"))
    )
    (net (code "16") (name "6P") (class "Default")
      (node (ref "J7") (pin "PWR") (pinfunction "PWR_PWR") (pintype "bidirectional"))
      (node (ref "RA2") (pin "4") (pinfunction "4_4") (pintype "passive"))
      (node (ref "U7") (pin "5") (pinfunction "IO4_5") (pintype "bidirectional"))
    )
    (net (code "17") (name "7N") (class "Default")
      (node (ref "J6") (pin "GND") (pinfunction "GND_GND") (pintype "bidirectional"))
      (node (ref "J6") (pin "GNDBREAK") (pinfunction "GNDBREAK_GNDBREAK") (pintype "bidirectional"))
      (node (ref "RA2") (pin "1") (pinfunction "1_1") (pintype "passive"))
      (node (ref "U6") (pin "4") (pinfunction "IO3_4") (pintype "bidirectional"))
    )
    (net (code "18") (name "7P") (class "Default")
      (node (ref "J6") (pin "PWR") (pinfunction "PWR_PWR") (pintype "bidirectional"))
      (node (ref "RA2") (pin "2") (pinfunction "2_2") (pintype "passive"))
      (node (ref "U7") (pin "1") (pinfunction "IO1_1") (pintype "bidirectional"))
    )
    (net (code "19") (name "8N") (class "Default")
      (node (ref "J5") (pin "GND") (pinfunction "GND_GND") (pintype "bidirectional"))
      (node (ref "J5") (pin "GNDBREAK") (pinfunction "GNDBREAK_GNDBREAK") (pintype "bidirectional"))
      (node (ref "RA1") (pin "3") (pinfunction "3_3") (pintype "passive"))
      (node (ref "U6") (pin "2") (pinfunction "IO2_2") (pintype "bidirectional"))
    )
    (net (code "20") (name "8P") (class "Default")
      (node (ref "J5") (pin "PWR") (pinfunction "PWR_PWR") (pintype "bidirectional"))
      (node (ref "RA1") (pin "4") (pinfunction "4_4") (pintype "passive"))
      (node (ref "U6") (pin "5") (pinfunction "IO4_5") (pintype "bidirectional"))
    )
    (net (code "21") (name "9N") (class "Default")
      (node (ref "J20") (pin "GND") (pinfunction "GND_GND") (pintype "bidirectional"))
      (node (ref "J20") (pin "GNDBREAK") (pinfunction "GNDBREAK_GNDBREAK") (pintype "bidirectional"))
      (node (ref "R14") (pin "1") (pinfunction "1_1") (pintype "passive"))
      (node (ref "U15") (pin "4") (pinfunction "IO3_4") (pintype "bidirectional"))
    )
    (net (code "22") (name "9P") (class "Default")
      (node (ref "J20") (pin "PWR") (pinfunction "PWR_PWR") (pintype "bidirectional"))
      (node (ref "R14") (pin "2") (pinfunction "2_2") (pintype "passive"))
      (node (ref "U16") (pin "1") (pinfunction "IO1_1") (pintype "bidirectional"))
    )
    (net (code "23") (name "10N") (class "Default")
      (node (ref "J19") (pin "GND") (pinfunction "GND_GND") (pintype "bidirectional"))
      (node (ref "J19") (pin "GNDBREAK") (pinfunction "GNDBREAK_GNDBREAK") (pintype "bidirectional"))
      (node (ref "RA8") (pin "3") (pinfunction "3_3") (pintype "passive"))
      (node (ref "U15") (pin "2") (pinfunction "IO2_2") (pintype "bidirectional"))
    )
    (net (code "24") (name "10P") (class "Default")
      (node (ref "J19") (pin "PWR") (pinfunction "PWR_PWR") (pintype "bidirectional"))
      (node (ref "RA8") (pin "4") (pinfunction "4_4") (pintype "passive"))
      (node (ref "U15") (pin "5") (pinfunction "IO4_5") (pintype "bidirectional"))
    )
    (net (code "25") (name "11N") (class "Default")
      (node (ref "J18") (pin "GND") (pinfunction "GND_GND") (pintype "bidirectional"))
      (node (ref "J18") (pin "GNDBREAK") (pinfunction "GNDBREAK_GNDBREAK") (pintype "bidirectional"))
      (node (ref "RA8") (pin "1") (pinfunction "1_1") (pintype "passive"))
      (node (ref "U14") (pin "4") (pinfunction "IO3_4") (pintype "bidirectional"))
    )
    (net (code "26") (name "11P") (class "Default")
      (node (ref "J18") (pin "PWR") (pinfunction "PWR_PWR") (pintype "bidirectional"))
      (node (ref "RA8") (pin "2") (pinfunction "2_2") (pintype "passive"))
      (node (ref "U15") (pin "1") (pinfunction "IO1_1") (pintype "bidirectional"))
    )
    (net (code "27") (name "12N") (class "Default")
      (node (ref "J17") (pin "GND") (pinfunction "GND_GND") (pintype "bidirectional"))
      (node (ref "J17") (pin "GNDBREAK") (pinfunction "GNDBREAK_GNDBREAK") (pintype "bidirectional"))
      (node (ref "RA7") (pin "3") (pinfunction "3_3") (pintype "passive"))
      (node (ref "U14") (pin "2") (pinfunction "IO2_2") (pintype "bidirectional"))
    )
    (net (code "28") (name "12P") (class "Default")
      (node (ref "J17") (pin "PWR") (pinfunction "PWR_PWR") (pintype "bidirectional"))
      (node (ref "RA7") (pin "4") (pinfunction "4_4") (pintype "passive"))
      (node (ref "U14") (pin "5") (pinfunction "IO4_5") (pintype "bidirectional"))
    )
    (net (code "29") (name "13N") (class "Default")
      (node (ref "J16") (pin "GND") (pinfunction "GND_GND") (pintype "bidirectional"))
      (node (ref "J16") (pin "GNDBREAK") (pinfunction "GNDBREAK_GNDBREAK") (pintype "bidirectional"))
      (node (ref "RA7") (pin "1") (pinfunction "1_1") (pintype "passive"))
      (node (ref "U13") (pin "4") (pinfunction "IO3_4") (pintype "bidirectional"))
    )
    (net (code "30") (name "13P") (class "Default")
      (node (ref "J16") (pin "PWR") (pinfunction "PWR_PWR") (pintype "bidirectional"))
      (node (ref "RA7") (pin "2") (pinfunction "2_2") (pintype "passive"))
      (node (ref "U14") (pin "1") (pinfunction "IO1_1") (pintype "bidirectional"))
    )
    (net (code "31") (name "14N") (class "Default")
      (node (ref "J15") (pin "GND") (pinfunction "GND_GND") (pintype "bidirectional"))
      (node (ref "J15") (pin "GNDBREAK") (pinfunction "GNDBREAK_GNDBREAK") (pintype "bidirectional"))
      (node (ref "RA6") (pin "3") (pinfunction "3_3") (pintype "passive"))
      (node (ref "U13") (pin "2") (pinfunction "IO2_2") (pintype "bidirectional"))
    )
    (net (code "32") (name "14P") (class "Default")
      (node (ref "J15") (pin "PWR") (pinfunction "PWR_PWR") (pintype "bidirectional"))
      (node (ref "RA6") (pin "4") (pinfunction "4_4") (pintype "passive"))
      (node (ref "U13") (pin "5") (pinfunction "IO4_5") (pintype "bidirectional"))
    )
    (net (code "33") (name "15N") (class "Default")
      (node (ref "J14") (pin "GND") (pinfunction "GND_GND") (pintype "bidirectional"))
      (node (ref "J14") (pin "GNDBREAK") (pinfunction "GNDBREAK_GNDBREAK") (pintype "bidirectional"))
      (node (ref "RA6") (pin "1") (pinfunction "1_1") (pintype "passive"))
      (node (ref "U12") (pin "4") (pinfunction "IO3_4") (pintype "bidirectional"))
    )
    (net (code "34") (name "15P") (class "Default")
      (node (ref "J14") (pin "PWR") (pinfunction "PWR_PWR") (pintype "bidirectional"))
      (node (ref "RA6") (pin "2") (pinfunction "2_2") (pintype "passive"))
      (node (ref "U13") (pin "1") (pinfunction "IO1_1") (pintype "bidirectional"))
    )
    (net (code "35") (name "16N") (class "Default")
      (node (ref "J13") (pin "GND") (pinfunction "GND_GND") (pintype "bidirectional"))
      (node (ref "J13") (pin "GNDBREAK") (pinfunction "GNDBREAK_GNDBREAK") (pintype "bidirectional"))
      (node (ref "RA5") (pin "3") (pinfunction "3_3") (pintype "passive"))
      (node (ref "U12") (pin "2") (pinfunction "IO2_2") (pintype "bidirectional"))
    )
    (net (code "36") (name "16P") (class "Default")
      (node (ref "J13") (pin "PWR") (pinfunction "PWR_PWR") (pintype "bidirectional"))
      (node (ref "RA5") (pin "4") (pinfunction "4_4") (pintype "passive"))
      (node (ref "U12") (pin "5") (pinfunction "IO4_5") (pintype "bidirectional"))
    )
    (net (code "37") (name "AIN1N") (class "Default")
      (node (ref "CA5") (pin "8") (pinfunction "8_8") (pintype "passive"))
      (node (ref "R45") (pin "8") (pinfunction "8_8") (pintype "passive"))
      (node (ref "U1") (pin "15") (pinfunction "IN1N_15") (pintype "input"))
    )
    (net (code "38") (name "AIN1P") (class "Default")
      (node (ref "CA5") (pin "7") (pinfunction "7_7") (pintype "passive"))
      (node (ref "R45") (pin "7") (pinfunction "7_7") (pintype "passive"))
      (node (ref "U1") (pin "16") (pinfunction "IN1P_16") (pintype "input"))
    )
    (net (code "39") (name "AIN2N") (class "Default")
      (node (ref "CA4") (pin "6") (pinfunction "6_6") (pintype "passive"))
      (node (ref "RA4") (pin "6") (pinfunction "6_6") (pintype "passive"))
      (node (ref "U1") (pin "13") (pinfunction "IN2N_13") (pintype "input"))
    )
    (net (code "40") (name "AIN2P") (class "Default")
      (node (ref "CA4") (pin "5") (pinfunction "5_5") (pintype "passive"))
      (node (ref "RA4") (pin "5") (pinfunction "5_5") (pintype "passive"))
      (node (ref "U1") (pin "14") (pinfunction "IN2P_14") (pintype "input"))
    )
    (net (code "41") (name "AIN3N") (class "Default")
      (node (ref "CA4") (pin "8") (pinfunction "8_8") (pintype "passive"))
      (node (ref "RA4") (pin "8") (pinfunction "8_8") (pintype "passive"))
      (node (ref "U1") (pin "11") (pinfunction "IN3N_11") (pintype "input"))
    )
    (net (code "42") (name "AIN3P") (class "Default")
      (node (ref "CA4") (pin "7") (pinfunction "7_7") (pintype "passive"))
      (node (ref "RA4") (pin "7") (pinfunction "7_7") (pintype "passive"))
      (node (ref "U1") (pin "12") (pinfunction "IN3P_12") (pintype "input"))
    )
    (net (code "43") (name "AIN4N") (class "Default")
      (node (ref "CA3") (pin "6") (pinfunction "6_6") (pintype "passive"))
      (node (ref "RA3") (pin "6") (pinfunction "6_6") (pintype "passive"))
      (node (ref "U1") (pin "9") (pinfunction "IN4N_9") (pintype "input"))
    )
    (net (code "44") (name "AIN4P") (class "Default")
      (node (ref "CA3") (pin "5") (pinfunction "5_5") (pintype "passive"))
      (node (ref "RA3") (pin "5") (pinfunction "5_5") (pintype "passive"))
      (node (ref "U1") (pin "10") (pinfunction "IN4P_10") (pintype "input"))
    )
    (net (code "45") (name "AIN5N") (class "Default")
      (node (ref "CA3") (pin "8") (pinfunction "8_8") (pintype "passive"))
      (node (ref "RA3") (pin "8") (pinfunction "8_8") (pintype "passive"))
      (node (ref "U1") (pin "7") (pinfunction "IN5N_7") (pintype "input"))
    )
    (net (code "46") (name "AIN5P") (class "Default")
      (node (ref "CA3") (pin "7") (pinfunction "7_7") (pintype "passive"))
      (node (ref "RA3") (pin "7") (pinfunction "7_7") (pintype "passive"))
      (node (ref "U1") (pin "8") (pinfunction "IN5P_8") (pintype "input"))
    )
    (net (code "47") (name "AIN6N") (class "Default")
      (node (ref "CA2") (pin "6") (pinfunction "6_6") (pintype "passive"))
      (node (ref "RA2") (pin "6") (pinfunction "6_6") (pintype "passive"))
      (node (ref "U1") (pin "5") (pinfunction "IN6N_5") (pintype "input"))
    )
    (net (code "48") (name "AIN6P") (class "Default")
      (node (ref "CA2") (pin "5") (pinfunction "5_5") (pintype "passive"))
      (node (ref "RA2") (pin "5") (pinfunction "5_5") (pintype "passive"))
      (node (ref "U1") (pin "6") (pinfunction "IN6P_6") (pintype "input"))
    )
    (net (code "49") (name "AIN7N") (class "Default")
      (node (ref "CA2") (pin "8") (pinfunction "8_8") (pintype "passive"))
      (node (ref "RA2") (pin "8") (pinfunction "8_8") (pintype "passive"))
      (node (ref "U1") (pin "3") (pinfunction "IN7N_3") (pintype "input"))
    )
    (net (code "50") (name "AIN7P") (class "Default")
      (node (ref "CA2") (pin "7") (pinfunction "7_7") (pintype "passive"))
      (node (ref "RA2") (pin "7") (pinfunction "7_7") (pintype "passive"))
      (node (ref "U1") (pin "4") (pinfunction "IN7P_4") (pintype "input"))
    )
    (net (code "51") (name "AIN8N") (class "Default")
      (node (ref "CA1") (pin "6") (pinfunction "6_6") (pintype "passive"))
      (node (ref "RA1") (pin "6") (pinfunction "6_6") (pintype "passive"))
      (node (ref "U1") (pin "1") (pinfunction "IN8N_1") (pintype "input"))
    )
    (net (code "52") (name "AIN8P") (class "Default")
      (node (ref "CA1") (pin "5") (pinfunction "5_5") (pintype "passive"))
      (node (ref "RA1") (pin "5") (pinfunction "5_5") (pintype "passive"))
      (node (ref "U1") (pin "2") (pinfunction "IN8P_2") (pintype "input"))
    )
    (net (code "53") (name "AIN9N") (class "Default")
      (node (ref "CA10") (pin "8") (pinfunction "8_8") (pintype "passive"))
      (node (ref "R14") (pin "8") (pinfunction "8_8") (pintype "passive"))
      (node (ref "U2") (pin "15") (pinfunction "IN1N_15") (pintype "input"))
    )
    (net (code "54") (name "AIN9P") (class "Default")
      (node (ref "CA10") (pin "7") (pinfunction "7_7") (pintype "passive"))
      (node (ref "R14") (pin "7") (pinfunction "7_7") (pintype "passive"))
      (node (ref "U2") (pin "16") (pinfunction "IN1P_16") (pintype "input"))
    )
    (net (code "55") (name "AIN10N") (class "Default")
      (node (ref "CA9") (pin "6") (pinfunction "6_6") (pintype "passive"))
      (node (ref "RA8") (pin "6") (pinfunction "6_6") (pintype "passive"))
      (node (ref "U2") (pin "13") (pinfunction "IN2N_13") (pintype "input"))
    )
    (net (code "56") (name "AIN10P") (class "Default")
      (node (ref "CA9") (pin "5") (pinfunction "5_5") (pintype "passive"))
      (node (ref "RA8") (pin "5") (pinfunction "5_5") (pintype "passive"))
      (node (ref "U2") (pin "14") (pinfunction "IN2P_14") (pintype "input"))
    )
    (net (code "57") (name "AIN11N") (class "Default")
      (node (ref "CA9") (pin "8") (pinfunction "8_8") (pintype "passive"))
      (node (ref "RA8") (pin "8") (pinfunction "8_8") (pintype "passive"))
      (node (ref "U2") (pin "11") (pinfunction "IN3N_11") (pintype "input"))
    )
    (net (code "58") (name "AIN11P") (class "Default")
      (node (ref "CA9") (pin "7") (pinfunction "7_7") (pintype "passive"))
      (node (ref "RA8") (pin "7") (pinfunction "7_7") (pintype "passive"))
      (node (ref "U2") (pin "12") (pinfunction "IN3P_12") (pintype "input"))
    )
    (net (code "59") (name "AIN12N") (class "Default")
      (node (ref "CA8") (pin "6") (pinfunction "6_6") (pintype "passive"))
      (node (ref "RA7") (pin "6") (pinfunction "6_6") (pintype "passive"))
      (node (ref "U2") (pin "9") (pinfunction "IN4N_9") (pintype "input"))
    )
    (net (code "60") (name "AIN12P") (class "Default")
      (node (ref "CA8") (pin "5") (pinfunction "5_5") (pintype "passive"))
      (node (ref "RA7") (pin "5") (pinfunction "5_5") (pintype "passive"))
      (node (ref "U2") (pin "10") (pinfunction "IN4P_10") (pintype "input"))
    )
    (net (code "61") (name "AIN13N") (class "Default")
      (node (ref "CA8") (pin "8") (pinfunction "8_8") (pintype "passive"))
      (node (ref "RA7") (pin "8") (pinfunction "8_8") (pintype "passive"))
      (node (ref "U2") (pin "7") (pinfunction "IN5N_7") (pintype "input"))
    )
    (net (code "62") (name "AIN13P") (class "Default")
      (node (ref "CA8") (pin "7") (pinfunction "7_7") (pintype "passive"))
      (node (ref "RA7") (pin "7") (pinfunction "7_7") (pintype "passive"))
      (node (ref "U2") (pin "8") (pinfunction "IN5P_8") (pintype "input"))
    )
    (net (code "63") (name "AIN14N") (class "Default")
      (node (ref "CA7") (pin "6") (pinfunction "6_6") (pintype "passive"))
      (node (ref "RA6") (pin "6") (pinfunction "6_6") (pintype "passive"))
      (node (ref "U2") (pin "5") (pinfunction "IN6N_5") (pintype "input"))
    )
    (net (code "64") (name "AIN14P") (class "Default")
      (node (ref "CA7") (pin "5") (pinfunction "5_5") (pintype "passive"))
      (node (ref "RA6") (pin "5") (pinfunction "5_5") (pintype "passive"))
      (node (ref "U2") (pin "6") (pinfunction "IN6P_6") (pintype "input"))
    )
    (net (code "65") (name "AIN15N") (class "Default")
      (node (ref "CA7") (pin "8") (pinfunction "8_8") (pintype "passive"))
      (node (ref "RA6") (pin "8") (pinfunction "8_8") (pintype "passive"))
      (node (ref "U2") (pin "3") (pinfunction "IN7N_3") (pintype "input"))
    )
    (net (code "66") (name "AIN15P") (class "Default")
      (node (ref "CA7") (pin "7") (pinfunction "7_7") (pintype "passive"))
      (node (ref "RA6") (pin "7") (pinfunction "7_7") (pintype "passive"))
      (node (ref "U2") (pin "4") (pinfunction "IN7P_4") (pintype "input"))
    )
    (net (code "67") (name "AIN16N") (class "Default")
      (node (ref "CA6") (pin "6") (pinfunction "6_6") (pintype "passive"))
      (node (ref "RA5") (pin "6") (pinfunction "6_6") (pintype "passive"))
      (node (ref "U2") (pin "1") (pinfunction "IN8N_1") (pintype "input"))
    )
    (net (code "68") (name "AIN16P") (class "Default")
      (node (ref "CA6") (pin "5") (pinfunction "5_5") (pintype "passive"))
      (node (ref "RA5") (pin "5") (pinfunction "5_5") (pintype "passive"))
      (node (ref "U2") (pin "2") (pinfunction "IN8P_2") (pintype "input"))
    )
    (net (code "69") (name "B1") (class "Default")
      (node (ref "A1") (pin "VB") (pinfunction "VB_VB") (pintype "passive"))
      (node (ref "JP3") (pin "3") (pinfunction "3_3") (pintype "passive"))
    )
    (net (code "70") (name "B2") (class "Default")
      (node (ref "A1") (pin "NR") (pinfunction "NR_NR") (pintype "passive"))
      (node (ref "JP3") (pin "4") (pinfunction "4_4") (pintype "passive"))
    )
    (net (code "71") (name "B5") (class "Default")
      (node (ref "A1") (pin "P$21") (pinfunction "P21_P$21") (pintype "passive"))
      (node (ref "JP2") (pin "1") (pinfunction "1_1") (pintype "passive"))
    )
    (net (code "72") (name "B6") (class "Default")
      (node (ref "A1") (pin "P$23") (pinfunction "P23_P$23") (pintype "passive"))
      (node (ref "JP2") (pin "3") (pinfunction "3_3") (pintype "passive"))
    )
    (net (code "73") (name "B7") (class "Default")
      (node (ref "A1") (pin "P$24") (pinfunction "P24_P$24") (pintype "passive"))
      (node (ref "JP2") (pin "4") (pinfunction "4_4") (pintype "passive"))
    )
    (net (code "74") (name "B8") (class "Default")
      (node (ref "A1") (pin "P$26") (pinfunction "P26_P$26") (pintype "passive"))
      (node (ref "JP2") (pin "6") (pinfunction "6_6") (pintype "passive"))
    )
    (net (code "75") (name "B9") (class "Default")
      (node (ref "A1") (pin "P$30") (pinfunction "P30_P$30") (pintype "passive"))
      (node (ref "JP2") (pin "10") (pinfunction "10_10") (pintype "passive"))
    )
    (net (code "76") (name "B10") (class "Default")
      (node (ref "A1") (pin "D+") (pinfunction "D+_D+") (pintype "passive"))
      (node (ref "JP2") (pin "11") (pinfunction "11_11") (pintype "passive"))
    )
    (net (code "77") (name "B11") (class "Default")
      (node (ref "A1") (pin "D-") (pinfunction "D-_D-") (pintype "passive"))
      (node (ref "JP2") (pin "12") (pinfunction "12_12") (pintype "passive"))
    )
    (net (code "78") (name "B12") (class "Default")
      (node (ref "A1") (pin "TD+") (pinfunction "TD+_TD+") (pintype "passive"))
      (node (ref "JP2") (pin "13") (pinfunction "13_13") (pintype "passive"))
    )
    (net (code "79") (name "B13") (class "Default")
      (node (ref "A1") (pin "TD-") (pinfunction "TD-_TD-") (pintype "passive"))
      (node (ref "JP2") (pin "14") (pinfunction "14_14") (pintype "passive"))
    )
    (net (code "80") (name "B14") (class "Default")
      (node (ref "A1") (pin "RD+") (pinfunction "RD+_RD+") (pintype "passive"))
      (node (ref "JP2") (pin "15") (pinfunction "15_15") (pintype "passive"))
    )
    (net (code "81") (name "B15") (class "Default")
      (node (ref "A1") (pin "RD-") (pinfunction "RD-_RD-") (pintype "passive"))
      (node (ref "JP2") (pin "16") (pinfunction "16_16") (pintype "passive"))
    )
    (net (code "82") (name "B16") (class "Default")
      (node (ref "A1") (pin "IF+") (pinfunction "IF+_IF+") (pintype "passive"))
      (node (ref "JP2") (pin "17") (pinfunction "17_17") (pintype "passive"))
    )
    (net (code "83") (name "B17") (class "Default")
      (node (ref "A1") (pin "IF-") (pinfunction "IF-_IF-") (pintype "passive"))
      (node (ref "JP2") (pin "18") (pinfunction "18_18") (pintype "passive"))
    )
    (net (code "84") (name "B18") (class "Default")
      (node (ref "A1") (pin "VU") (pinfunction "VU_VU") (pintype "passive"))
      (node (ref "JP2") (pin "19") (pinfunction "19_19") (pintype "passive"))
    )
    (net (code "85") (name "BATT_SWITCH") (class "Default")
      (node (ref "R8") (pin "1") (pinfunction "1_1") (pintype "passive"))
      (node (ref "SW1") (pin "3") (pinfunction "3_3") (pintype "passive"))
      (node (ref "SW2") (pin "3") (pinfunction "3_3") (pintype "passive"))
    )
    (net (code "86") (name "BIAS") (class "Default")
      (node (ref "C25") (pin "2") (pinfunction "2_2") (pintype "passive"))
      (node (ref "J21") (pin "GND") (pinfunction "GND_GND") (pintype "bidirectional"))
      (node (ref "J21") (pin "GNDBREAK") (pinfunction "GNDBREAK_GNDBREAK") (pintype "bidirectional"))
      (node (ref "J21") (pin "PWR") (pinfunction "PWR_PWR") (pintype "bidirectional"))
      (node (ref "R12") (pin "2") (pinfunction "2_2") (pintype "passive"))
      (node (ref "RA1") (pin "1") (pinfunction "1_1") (pintype "passive"))
      (node (ref "U1") (pin "62") (pinfunction "BIASIN_62") (pintype "input"))
      (node (ref "U1") (pin "63") (pinfunction "BIASOUT_63") (pintype "output"))
      (node (ref "U11") (pin "4") (pinfunction "IO3_4") (pintype "bidirectional"))
    )
    (net (code "87") (name "BIAS_1") (class "Default")
      (node (ref "J23") (pin "GND") (pinfunction "GND_GND") (pintype "bidirectional"))
      (node (ref "J23") (pin "GNDBREAK") (pinfunction "GNDBREAK_GNDBREAK") (pintype "bidirectional"))
      (node (ref "J23") (pin "PWR") (pinfunction "PWR_PWR") (pintype "bidirectional"))
      (node (ref "RA5") (pin "1") (pinfunction "1_1") (pintype "passive"))
      (node (ref "U17") (pin "4") (pinfunction "IO3_4") (pintype "bidirectional"))
    )
    (net (code "88") (name "BIAS_DRV") (class "Default")
      (node (ref "C25") (pin "1") (pinfunction "1_1") (pintype "passive"))
      (node (ref "CA1") (pin "8") (pinfunction "8_8") (pintype "passive"))
      (node (ref "R12") (pin "1") (pinfunction "1_1") (pintype "passive"))
      (node (ref "RA1") (pin "8") (pinfunction "8_8") (pintype "passive"))
    )
    (net (code "89") (name "BIAS_DRV_1") (class "Default")
      (node (ref "C37") (pin "1") (pinfunction "1_1") (pintype "passive"))
      (node (ref "CA6") (pin "8") (pinfunction "8_8") (pintype "passive"))
      (node (ref "R13") (pin "1") (pinfunction "1_1") (pintype "passive"))
      (node (ref "RA5") (pin "8") (pinfunction "8_8") (pintype "passive"))
    )
    (net (code "90") (name "BIAS_INV") (class "Default")
      (node (ref "JP4") (pin "2") (pinfunction "2_2") (pintype "passive"))
      (node (ref "U1") (pin "61") (pinfunction "BIASINV_61") (pintype "bidirectional"))
    )
    (net (code "91") (name "BIAS_INV_1") (class "Default")
      (node (ref "U2") (pin "61") (pinfunction "BIASINV_61") (pintype "bidirectional"))
    )
    (net (code "92") (name "BLE_EN") (class "Default")
      (node (ref "A1") (pin "P$17") (pinfunction "P17_P$17") (pintype "passive"))
      (node (ref "JP3") (pin "17") (pinfunction "17_17") (pintype "passive"))
      (node (ref "JP7") (pin "1") (pinfunction "1_1") (pintype "passive"))
    )
    (net (code "93") (name "BLE_RX") (class "Default")
      (node (ref "A1") (pin "P$9") (pinfunction "P9_P$9") (pintype "passive"))
      (node (ref "JP3") (pin "9") (pinfunction "9_9") (pintype "passive"))
      (node (ref "JP7") (pin "5") (pinfunction "5_5") (pintype "passive"))
    )
    (net (code "94") (name "BLE_STATE") (class "Default")
      (node (ref "A1") (pin "P$18") (pinfunction "P18_P$18") (pintype "passive"))
      (node (ref "JP3") (pin "18") (pinfunction "18_18") (pintype "passive"))
      (node (ref "JP7") (pin "6") (pinfunction "6_6") (pintype "passive"))
    )
    (net (code "95") (name "BLE_TX") (class "Default")
      (node (ref "A1") (pin "P$10") (pinfunction "P10_P$10") (pintype "passive"))
      (node (ref "JP3") (pin "10") (pinfunction "10_10") (pintype "passive"))
      (node (ref "JP7") (pin "4") (pinfunction "4_4") (pintype "passive"))
    )
    (net (code "96") (name "CLK_ADS") (class "Default")
      (node (ref "R18") (pin "2") (pinfunction "2_2") (pintype "passive"))
      (node (ref "R19") (pin "2") (pinfunction "2_2") (pintype "passive"))
      (node (ref "U1") (pin "37") (pinfunction "CLK_37") (pintype "input"))
    )
    (net (code "97") (name "DEBUG_1") (class "Default")
      (node (ref "A1") (pin "P$29") (pinfunction "P29_P$29") (pintype "passive"))
      (node (ref "JP2") (pin "2") (pinfunction "2_2") (pintype "passive"))
      (node (ref "R15") (pin "1") (pinfunction "1_1") (pintype "passive"))
    )
    (net (code "98") (name "DEBUG_2") (class "Default")
      (node (ref "A1") (pin "P$25") (pinfunction "P25_P$25") (pintype "passive"))
      (node (ref "JP2") (pin "5") (pinfunction "5_5") (pintype "passive"))
      (node (ref "R16") (pin "1") (pinfunction "1_1") (pintype "passive"))
    )
    (net (code "99") (name "DEBUG_3") (class "Default")
      (node (ref "A1") (pin "P$22") (pinfunction "P22_P$22") (pintype "passive"))
      (node (ref "JP2") (pin "9") (pinfunction "9_9") (pintype "passive"))
      (node (ref "R17") (pin "1") (pinfunction "1_1") (pintype "passive"))
    )
    (net (code "100") (name "GND") (class "Default")
      (node (ref "A1") (pin "GND") (pinfunction "GND_GND") (pintype "passive"))
      (node (ref "C1") (pin "2") (pinfunction "2_2") (pintype "passive"))
      (node (ref "C11") (pin "2") (pinfunction "2_2") (pintype "passive"))
      (node (ref "C12") (pin "2") (pinfunction "2_2") (pintype "passive"))
      (node (ref "C13") (pin "2") (pinfunction "2_2") (pintype "passive"))
      (node (ref "C14") (pin "2") (pinfunction "2_2") (pintype "passive"))
      (node (ref "C15") (pin "2") (pinfunction "2_2") (pintype "passive"))
      (node (ref "C16") (pin "2") (pinfunction "2_2") (pintype "passive"))
      (node (ref "C17") (pin "2") (pinfunction "2_2") (pintype "passive"))
      (node (ref "C18") (pin "2") (pinfunction "2_2") (pintype "passive"))
      (node (ref "C19") (pin "2") (pinfunction "2_2") (pintype "passive"))
      (node (ref "C2") (pin "2") (pinfunction "2_2") (pintype "passive"))
      (node (ref "C20") (pin "2") (pinfunction "2_2") (pintype "passive"))
      (node (ref "C21") (pin "2") (pinfunction "2_2") (pintype "passive"))
      (node (ref "C22") (pin "2") (pinfunction "2_2") (pintype "passive"))
      (node (ref "C23") (pin "2") (pinfunction "2_2") (pintype "passive"))
      (node (ref "C24") (pin "2") (pinfunction "2_2") (pintype "passive"))
      (node (ref "C26") (pin "2") (pinfunction "2_2") (pintype "passive"))
      (node (ref "C27") (pin "2") (pinfunction "2_2") (pintype "passive"))
      (node (ref "C28") (pin "2") (pinfunction "2_2") (pintype "passive"))
      (node (ref "C29") (pin "2") (pinfunction "2_2") (pintype "passive"))
      (node (ref "C3") (pin "2") (pinfunction "2_2") (pintype "passive"))
      (node (ref "C30") (pin "2") (pinfunction "2_2") (pintype "passive"))
      (node (ref "C31") (pin "2") (pinfunction "2_2") (pintype "passive"))
      (node (ref "C32") (pin "2") (pinfunction "2_2") (pintype "passive"))
      (node (ref "C33") (pin "2") (pinfunction "2_2") (pintype "passive"))
      (node (ref "C34") (pin "2") (pinfunction "2_2") (pintype "passive"))
      (node (ref "C35") (pin "2") (pinfunction "2_2") (pintype "passive"))
      (node (ref "C36") (pin "2") (pinfunction "2_2") (pintype "passive"))
      (node (ref "C4") (pin "2") (pinfunction "2_2") (pintype "passive"))
      (node (ref "C5") (pin "2") (pinfunction "2_2") (pintype "passive"))
      (node (ref "C6") (pin "2") (pinfunction "2_2") (pintype "passive"))
      (node (ref "C7") (pin "2") (pinfunction "2_2") (pintype "passive"))
      (node (ref "C9") (pin "2") (pinfunction "2_2") (pintype "passive"))
      (node (ref "CA1") (pin "1") (pinfunction "1_1") (pintype "passive"))
      (node (ref "CA1") (pin "2") (pinfunction "2_2") (pintype "passive"))
      (node (ref "CA1") (pin "3") (pinfunction "3_3") (pintype "passive"))
      (node (ref "CA1") (pin "4") (pinfunction "4_4") (pintype "passive"))
      (node (ref "CA1") (pin "7") (pinfunction "7_7") (pintype "passive"))
      (node (ref "CA10") (pin "1") (pinfunction "1_1") (pintype "passive"))
      (node (ref "CA10") (pin "2") (pinfunction "2_2") (pintype "passive"))
      (node (ref "CA10") (pin "3") (pinfunction "3_3") (pintype "passive"))
      (node (ref "CA10") (pin "4") (pinfunction "4_4") (pintype "passive"))
      (node (ref "CA2") (pin "1") (pinfunction "1_1") (pintype "passive"))
      (node (ref "CA2") (pin "2") (pinfunction "2_2") (pintype "passive"))
      (node (ref "CA2") (pin "3") (pinfunction "3_3") (pintype "passive"))
      (node (ref "CA2") (pin "4") (pinfunction "4_4") (pintype "passive"))
      (node (ref "CA3") (pin "1") (pinfunction "1_1") (pintype "passive"))
      (node (ref "CA3") (pin "2") (pinfunction "2_2") (pintype "passive"))
      (node (ref "CA3") (pin "3") (pinfunction "3_3") (pintype "passive"))
      (node (ref "CA3") (pin "4") (pinfunction "4_4") (pintype "passive"))
      (node (ref "CA4") (pin "1") (pinfunction "1_1") (pintype "passive"))
      (node (ref "CA4") (pin "2") (pinfunction "2_2") (pintype "passive"))
      (node (ref "CA4") (pin "3") (pinfunction "3_3") (pintype "passive"))
      (node (ref "CA4") (pin "4") (pinfunction "4_4") (pintype "passive"))
      (node (ref "CA5") (pin "1") (pinfunction "1_1") (pintype "passive"))
      (node (ref "CA5") (pin "2") (pinfunction "2_2") (pintype "passive"))
      (node (ref "CA5") (pin "3") (pinfunction "3_3") (pintype "passive"))
      (node (ref "CA5") (pin "4") (pinfunction "4_4") (pintype "passive"))
      (node (ref "CA6") (pin "1") (pinfunction "1_1") (pintype "passive"))
      (node (ref "CA6") (pin "2") (pinfunction "2_2") (pintype "passive"))
      (node (ref "CA6") (pin "3") (pinfunction "3_3") (pintype "passive"))
      (node (ref "CA6") (pin "4") (pinfunction "4_4") (pintype "passive"))
      (node (ref "CA6") (pin "7") (pinfunction "7_7") (pintype "passive"))
      (node (ref "CA7") (pin "1") (pinfunction "1_1") (pintype "passive"))
      (node (ref "CA7") (pin "2") (pinfunction "2_2") (pintype "passive"))
      (node (ref "CA7") (pin "3") (pinfunction "3_3") (pintype "passive"))
      (node (ref "CA7") (pin "4") (pinfunction "4_4") (pintype "passive"))
      (node (ref "CA8") (pin "1") (pinfunction "1_1") (pintype "passive"))
      (node (ref "CA8") (pin "2") (pinfunction "2_2") (pintype "passive"))
      (node (ref "CA8") (pin "3") (pinfunction "3_3") (pintype "passive"))
      (node (ref "CA8") (pin "4") (pinfunction "4_4") (pintype "passive"))
      (node (ref "CA9") (pin "1") (pinfunction "1_1") (pintype "passive"))
      (node (ref "CA9") (pin "2") (pinfunction "2_2") (pintype "passive"))
      (node (ref "CA9") (pin "3") (pinfunction "3_3") (pintype "passive"))
      (node (ref "CA9") (pin "4") (pinfunction "4_4") (pintype "passive"))
      (node (ref "D1") (pin "C") (pinfunction "C_C") (pintype "passive"))
      (node (ref "D2") (pin "C") (pinfunction "C_C") (pintype "passive"))
      (node (ref "D3") (pin "C") (pinfunction "C_C") (pintype "passive"))
      (node (ref "D4") (pin "C") (pinfunction "C_C") (pintype "passive"))
      (node (ref "D5") (pin "C") (pinfunction "C_C") (pintype "passive"))
      (node (ref "D6") (pin "C") (pinfunction "C_C") (pintype "passive"))
      (node (ref "D7") (pin "C") (pinfunction "C_C") (pintype "passive"))
      (node (ref "J1") (pin "11") (pinfunction "11_11") (pintype "passive"))
      (node (ref "J1") (pin "12") (pinfunction "12_12") (pintype "passive"))
      (node (ref "J1") (pin "6") (pinfunction "6_6") (pintype "passive"))
      (node (ref "J3") (pin "P$1") (pinfunction "1_P$1") (pintype "passive"))
      (node (ref "J4") (pin "GND") (pinfunction "GND_GND") (pintype "bidirectional"))
      (node (ref "J4") (pin "GNDBREAK") (pinfunction "GNDBREAK_GNDBREAK") (pintype "bidirectional"))
      (node (ref "JP1") (pin "1") (pinfunction "1_1") (pintype "passive"))
      (node (ref "JP3") (pin "1") (pinfunction "1_1") (pintype "passive"))
      (node (ref "JP4") (pin "1") (pinfunction "1_1") (pintype "passive"))
      (node (ref "JP7") (pin "3") (pinfunction "3_3") (pintype "passive"))
      (node (ref "R3") (pin "2") (pinfunction "2_2") (pintype "passive"))
      (node (ref "RA1") (pin "2") (pinfunction "2_2") (pintype "passive"))
      (node (ref "RA1") (pin "7") (pinfunction "7_7") (pintype "passive"))
      (node (ref "RA5") (pin "2") (pinfunction "2_2") (pintype "passive"))
      (node (ref "RA5") (pin "7") (pinfunction "7_7") (pintype "passive"))
      (node (ref "U1") (pin "20") (pinfunction "AVSS_2_20") (pintype "power_in"))
      (node (ref "U1") (pin "23") (pinfunction "AVSS_3_23") (pintype "power_in"))
      (node (ref "U1") (pin "25") (pinfunction "VREFN_25") (pintype "input"))
      (node (ref "U1") (pin "31") (pinfunction "RESV1_31") (pintype "input"))
      (node (ref "U1") (pin "32") (pinfunction "AVSS_4_32") (pintype "power_in"))
      (node (ref "U1") (pin "33") (pinfunction "DGND_2_33") (pintype "power_in"))
      (node (ref "U1") (pin "41") (pinfunction "DAISY_IN_41") (pintype "input"))
      (node (ref "U1") (pin "49") (pinfunction "DGND_3_49") (pintype "power_in"))
      (node (ref "U1") (pin "51") (pinfunction "DGND_51") (pintype "power_in"))
      (node (ref "U1") (pin "53") (pinfunction "AVSS1_53") (pintype "power_in"))
      (node (ref "U1") (pin "57") (pinfunction "AVSS_5_57") (pintype "power_in"))
      (node (ref "U1") (pin "58") (pinfunction "AVSS_58") (pintype "power_in"))
      (node (ref "U1") (pin "60") (pinfunction "BIASREF_60") (pintype "input"))
      (node (ref "U1") (pin "64") (pinfunction "RESERVED_64") (pintype "output"))
      (node (ref "U10") (pin "3") (pinfunction "GND_3") (pintype "power_in"))
      (node (ref "U11") (pin "1") (pinfunction "IO1_1") (pintype "bidirectional"))
      (node (ref "U11") (pin "3") (pinfunction "GND_3") (pintype "power_in"))
      (node (ref "U12") (pin "3") (pinfunction "GND_3") (pintype "power_in"))
      (node (ref "U13") (pin "3") (pinfunction "GND_3") (pintype "power_in"))
      (node (ref "U14") (pin "3") (pinfunction "GND_3") (pintype "power_in"))
      (node (ref "U15") (pin "3") (pinfunction "GND_3") (pintype "power_in"))
      (node (ref "U16") (pin "3") (pinfunction "GND_3") (pintype "power_in"))
      (node (ref "U17") (pin "1") (pinfunction "IO1_1") (pintype "bidirectional"))
      (node (ref "U17") (pin "3") (pinfunction "GND_3") (pintype "power_in"))
      (node (ref "U2") (pin "20") (pinfunction "AVSS_2_20") (pintype "power_in"))
      (node (ref "U2") (pin "23") (pinfunction "AVSS_3_23") (pintype "power_in"))
      (node (ref "U2") (pin "25") (pinfunction "VREFN_25") (pintype "input"))
      (node (ref "U2") (pin "31") (pinfunction "RESV1_31") (pintype "input"))
      (node (ref "U2") (pin "32") (pinfunction "AVSS_4_32") (pintype "power_in"))
      (node (ref "U2") (pin "33") (pinfunction "DGND_2_33") (pintype "power_in"))
      (node (ref "U2") (pin "41") (pinfunction "DAISY_IN_41") (pintype "input"))
      (node (ref "U2") (pin "49") (pinfunction "DGND_3_49") (pintype "power_in"))
      (node (ref "U2") (pin "51") (pinfunction "DGND_51") (pintype "power_in"))
      (node (ref "U2") (pin "53") (pinfunction "AVSS1_53") (pintype "power_in"))
      (node (ref "U2") (pin "57") (pinfunction "AVSS_5_57") (pintype "power_in"))
      (node (ref "U2") (pin "58") (pinfunction "AVSS_58") (pintype "power_in"))
      (node (ref "U2") (pin "60") (pinfunction "BIASREF_60") (pintype "input"))
      (node (ref "U2") (pin "64") (pinfunction "RESERVED_64") (pintype "output"))
      (node (ref "U3") (pin "11") (pinfunction "PGND2_11") (pintype "passive"))
      (node (ref "U3") (pin "3") (pinfunction "AGND_3") (pintype "passive"))
      (node (ref "U3") (pin "6") (pinfunction "MODE/SYNC_6") (pintype "passive"))
      (node (ref "U3") (pin "9") (pinfunction "PGND1_9") (pintype "passive"))
      (node (ref "U5") (pin "2") (pinfunction "GND_2") (pintype "passive"))
      (node (ref "U6") (pin "3") (pinfunction "GND_3") (pintype "power_in"))
      (node (ref "U7") (pin "3") (pinfunction "GND_3") (pintype "power_in"))
      (node (ref "U8") (pin "3") (pinfunction "GND_3") (pintype "power_in"))
      (node (ref "U9") (pin "3") (pinfunction "GND_3") (pintype "power_in"))
    )
    (net (code "101") (name "MISO_ADS") (class "Default")
      (node (ref "A1") (pin "P$6") (pinfunction "P6_P$6") (pintype "passive"))
      (node (ref "JP3") (pin "6") (pinfunction "6_6") (pintype "passive"))
      (node (ref "U1") (pin "43") (pinfunction "DOUT_43") (pintype "output"))
      (node (ref "U2") (pin "43") (pinfunction "DOUT_43") (pintype "output"))
    )
    (net (code "102") (name "MISO_SD") (class "Default")
      (node (ref "A1") (pin "P$12") (pinfunction "P12_P$12") (pintype "passive"))
      (node (ref "J1") (pin "7") (pinfunction "7_7") (pintype "passive"))
      (node (ref "JP3") (pin "12") (pinfunction "12_12") (pintype "passive"))
    )
    (net (code "103") (name "MOSI_ADS") (class "Default")
      (node (ref "A1") (pin "P$5") (pinfunction "P5_P$5") (pintype "passive"))
      (node (ref "JP3") (pin "5") (pinfunction "5_5") (pintype "passive"))
      (node (ref "U1") (pin "34") (pinfunction "DIN_34") (pintype "input"))
      (node (ref "U2") (pin "34") (pinfunction "DIN_34") (pintype "input"))
    )
    (net (code "104") (name "MOSI_SD") (class "Default")
      (node (ref "A1") (pin "P$11") (pinfunction "P11_P$11") (pintype "passive"))
      (node (ref "J1") (pin "3") (pinfunction "3_3") (pintype "passive"))
      (node (ref "JP3") (pin "11") (pinfunction "11_11") (pintype "passive"))
    )
    (net (code "105") (name "Net-(C10-Pad1)") (class "Default")
      (node (ref "C10") (pin "1") (pinfunction "1_1") (pintype "passive"))
      (node (ref "R5") (pin "2") (pinfunction "2_2") (pintype "passive"))
    )
    (net (code "106") (name "Net-(D1-PadA)") (class "Default")
      (node (ref "D1") (pin "A") (pinfunction "A_A") (pintype "passive"))
      (node (ref "R8") (pin "2") (pinfunction "2_2") (pintype "passive"))
    )
    (net (code "107") (name "Net-(D2-PadA)") (class "Default")
      (node (ref "D2") (pin "A") (pinfunction "A_A") (pintype "passive"))
      (node (ref "R9") (pin "2") (pinfunction "2_2") (pintype "passive"))
    )
    (net (code "108") (name "Net-(D3-PadA)") (class "Default")
      (node (ref "D3") (pin "A") (pinfunction "A_A") (pintype "passive"))
      (node (ref "R10") (pin "2") (pinfunction "2_2") (pintype "passive"))
    )
    (net (code "109") (name "Net-(D4-PadA)") (class "Default")
      (node (ref "D4") (pin "A") (pinfunction "A_A") (pintype "passive"))
      (node (ref "R11") (pin "2") (pinfunction "2_2") (pintype "passive"))
    )
    (net (code "110") (name "Net-(D5-PadA)") (class "Default")
      (node (ref "D5") (pin "A") (pinfunction "A_A") (pintype "passive"))
      (node (ref "R16") (pin "2") (pinfunction "2_2") (pintype "passive"))
    )
    (net (code "111") (name "Net-(D6-PadA)") (class "Default")
      (node (ref "D6") (pin "A") (pinfunction "A_A") (pintype "passive"))
      (node (ref "R17") (pin "2") (pinfunction "2_2") (pintype "passive"))
    )
    (net (code "112") (name "Net-(D7-PadA)") (class "Default")
      (node (ref "D7") (pin "A") (pinfunction "A_A") (pintype "passive"))
      (node (ref "R15") (pin "2") (pinfunction "2_2") (pintype "passive"))
    )
    (net (code "113") (name "Net-(J2-1)") (class "Default")
      (node (ref "J2") (pin "P$1") (pinfunction "1_P$1") (pintype "passive"))
      (node (ref "SW1") (pin "1") (pinfunction "1_1") (pintype "passive"))
    )
    (net (code "114") (name "Net-(JP6-Pad1)") (class "Default")
      (node (ref "JP6") (pin "1") (pinfunction "1_1") (pintype "passive"))
      (node (ref "R18") (pin "1") (pinfunction "1_1") (pintype "passive"))
    )
    (net (code "115") (name "Net-(U1-VCAP1)") (class "Default")
      (node (ref "C22") (pin "1") (pinfunction "1_1") (pintype "passive"))
      (node (ref "U1") (pin "28") (pinfunction "VCAP1_28") (pintype "passive"))
    )
    (net (code "116") (name "Net-(U1-VCAP2)") (class "Default")
      (node (ref "C21") (pin "1") (pinfunction "1_1") (pintype "passive"))
      (node (ref "U1") (pin "30") (pinfunction "VCAP2_30") (pintype "passive"))
    )
    (net (code "117") (name "Net-(U1-VCAP3)") (class "Default")
      (node (ref "C18") (pin "1") (pinfunction "1_1") (pintype "passive"))
      (node (ref "C19") (pin "1") (pinfunction "1_1") (pintype "passive"))
      (node (ref "U1") (pin "55") (pinfunction "VCAP3_55") (pintype "passive"))
    )
    (net (code "118") (name "Net-(U1-VCAP4)") (class "Default")
      (node (ref "C20") (pin "1") (pinfunction "1_1") (pintype "passive"))
      (node (ref "U1") (pin "26") (pinfunction "VCAP4_26") (pintype "output"))
    )
    (net (code "119") (name "Net-(U2-BIASIN)") (class "Default")
      (node (ref "C37") (pin "2") (pinfunction "2_2") (pintype "passive"))
      (node (ref "R13") (pin "2") (pinfunction "2_2") (pintype "passive"))
      (node (ref "U2") (pin "62") (pinfunction "BIASIN_62") (pintype "input"))
      (node (ref "U2") (pin "63") (pinfunction "BIASOUT_63") (pintype "output"))
    )
    (net (code "120") (name "Net-(U2-CLK)") (class "Default")
      (node (ref "R19") (pin "1") (pinfunction "1_1") (pintype "passive"))
      (node (ref "U2") (pin "37") (pinfunction "CLK_37") (pintype "input"))
    )
    (net (code "121") (name "Net-(U2-VCAP1)") (class "Default")
      (node (ref "C34") (pin "1") (pinfunction "1_1") (pintype "passive"))
      (node (ref "U2") (pin "28") (pinfunction "VCAP1_28") (pintype "passive"))
    )
    (net (code "122") (name "Net-(U2-VCAP2)") (class "Default")
      (node (ref "C33") (pin "1") (pinfunction "1_1") (pintype "passive"))
      (node (ref "U2") (pin "30") (pinfunction "VCAP2_30") (pintype "passive"))
    )
    (net (code "123") (name "Net-(U2-VCAP3)") (class "Default")
      (node (ref "C30") (pin "1") (pinfunction "1_1") (pintype "passive"))
      (node (ref "C31") (pin "1") (pinfunction "1_1") (pintype "passive"))
      (node (ref "U2") (pin "55") (pinfunction "VCAP3_55") (pintype "passive"))
    )
    (net (code "124") (name "Net-(U2-VCAP4)") (class "Default")
      (node (ref "C32") (pin "1") (pinfunction "1_1") (pintype "passive"))
      (node (ref "U2") (pin "26") (pinfunction "VCAP4_26") (pintype "output"))
    )
    (net (code "125") (name "Net-(U3-CBOOT)") (class "Default")
      (node (ref "C8") (pin "2") (pinfunction "2_2") (pintype "passive"))
      (node (ref "R2") (pin "1") (pinfunction "1_1") (pintype "passive"))
      (node (ref "U3") (pin "14") (pinfunction "CBOOT_14") (pintype "passive"))
    )
    (net (code "126") (name "Net-(U3-EN)") (class "Default")
      (node (ref "R1") (pin "1") (pinfunction "1_1") (pintype "passive"))
      (node (ref "U3") (pin "7") (pinfunction "EN_7") (pintype "passive"))
    )
    (net (code "127") (name "Net-(U3-FB)") (class "Default")
      (node (ref "C10") (pin "2") (pinfunction "2_2") (pintype "passive"))
      (node (ref "R3") (pin "1") (pinfunction "1_1") (pintype "passive"))
      (node (ref "R4") (pin "2") (pinfunction "2_2") (pintype "passive"))
      (node (ref "U3") (pin "4") (pinfunction "FB_4") (pintype "passive"))
    )
    (net (code "128") (name "Net-(U3-RBOOT)") (class "Default")
      (node (ref "R2") (pin "2") (pinfunction "2_2") (pintype "passive"))
      (node (ref "U3") (pin "13") (pinfunction "RBOOT_13") (pintype "passive"))
    )
    (net (code "129") (name "Net-(U3-SW)") (class "Default")
      (node (ref "C8") (pin "1") (pinfunction "1_1") (pintype "passive"))
      (node (ref "L1") (pin "1") (pinfunction "1_1") (pintype "passive"))
      (node (ref "U3") (pin "10") (pinfunction "SW_10") (pintype "passive"))
    )
    (net (code "130") (name "Net-(U3-VCC)") (class "Default")
      (node (ref "C9") (pin "1") (pinfunction "1_1") (pintype "passive"))
      (node (ref "U3") (pin "2") (pinfunction "VCC_2") (pintype "power_in"))
    )
    (net (code "131") (name "Net-(U3-VIN1)") (class "Default")
      (node (ref "C4") (pin "1") (pinfunction "1_1") (pintype "passive"))
      (node (ref "C5") (pin "1") (pinfunction "1_1") (pintype "passive"))
      (node (ref "C6") (pin "1") (pinfunction "1_1") (pintype "passive"))
      (node (ref "C7") (pin "1") (pinfunction "1_1") (pintype "passive"))
      (node (ref "R1") (pin "2") (pinfunction "2_2") (pintype "passive"))
      (node (ref "SW2") (pin "1") (pinfunction "1_1") (pintype "passive"))
      (node (ref "U3") (pin "12") (pinfunction "VIN2_12") (pintype "input"))
      (node (ref "U3") (pin "8") (pinfunction "VIN1_8") (pintype "input"))
    )
    (net (code "132") (name "Net-(U5-BYPASS)") (class "Default")
      (node (ref "C12") (pin "1") (pinfunction "1_1") (pintype "passive"))
      (node (ref "U5") (pin "4") (pinfunction "BYPASS_4") (pintype "passive"))
    )
    (net (code "133") (name "SCK_SD") (class "Default")
      (node (ref "A1") (pin "P$13") (pinfunction "P13_P$13") (pintype "passive"))
      (node (ref "J1") (pin "5") (pinfunction "5_5") (pintype "passive"))
      (node (ref "JP3") (pin "13") (pinfunction "13_13") (pintype "passive"))
    )
    (net (code "134") (name "SCLK_ADS") (class "Default")
      (node (ref "A1") (pin "P$7") (pinfunction "P7_P$7") (pintype "passive"))
      (node (ref "JP3") (pin "7") (pinfunction "7_7") (pintype "passive"))
      (node (ref "U1") (pin "40") (pinfunction "SCLK_40") (pintype "input"))
      (node (ref "U2") (pin "40") (pinfunction "SCLK_40") (pintype "input"))
    )
    (net (code "135") (name "SCL_IMU") (class "Default")
      (node (ref "A1") (pin "P$27") (pinfunction "P27_P$27") (pintype "passive"))
      (node (ref "JP1") (pin "4") (pinfunction "4_4") (pintype "passive"))
      (node (ref "JP2") (pin "7") (pinfunction "7_7") (pintype "passive"))
    )
    (net (code "136") (name "SDA_IMU") (class "Default")
      (node (ref "A1") (pin "P$28") (pinfunction "P28_P$28") (pintype "passive"))
      (node (ref "JP1") (pin "3") (pinfunction "3_3") (pintype "passive"))
      (node (ref "JP2") (pin "8") (pinfunction "8_8") (pintype "passive"))
    )
    (net (code "137") (name "SRB1") (class "Default")
      (node (ref "CA5") (pin "5") (pinfunction "5_5") (pintype "passive"))
      (node (ref "R45") (pin "5") (pinfunction "5_5") (pintype "passive"))
      (node (ref "U1") (pin "17") (pinfunction "SRB1_17") (pintype "bidirectional"))
    )
    (net (code "138") (name "SRB1_1") (class "Default")
      (node (ref "CA10") (pin "5") (pinfunction "5_5") (pintype "passive"))
      (node (ref "R14") (pin "5") (pinfunction "5_5") (pintype "passive"))
      (node (ref "U2") (pin "17") (pinfunction "SRB1_17") (pintype "bidirectional"))
    )
    (net (code "139") (name "SRB1_OUT") (class "Default")
      (node (ref "J22") (pin "GND") (pinfunction "GND_GND") (pintype "bidirectional"))
      (node (ref "J22") (pin "GNDBREAK") (pinfunction "GNDBREAK_GNDBREAK") (pintype "bidirectional"))
      (node (ref "R45") (pin "4") (pinfunction "4_4") (pintype "passive"))
      (node (ref "U10") (pin "5") (pinfunction "IO4_5") (pintype "bidirectional"))
    )
    (net (code "140") (name "SRB1_OUT_1") (class "Default")
      (node (ref "J24") (pin "GND") (pinfunction "GND_GND") (pintype "bidirectional"))
      (node (ref "J24") (pin "GNDBREAK") (pinfunction "GNDBREAK_GNDBREAK") (pintype "bidirectional"))
      (node (ref "R14") (pin "4") (pinfunction "4_4") (pintype "passive"))
      (node (ref "U16") (pin "5") (pinfunction "IO4_5") (pintype "bidirectional"))
    )
    (net (code "141") (name "SRB2") (class "Default")
      (node (ref "CA5") (pin "6") (pinfunction "6_6") (pintype "passive"))
      (node (ref "R45") (pin "6") (pinfunction "6_6") (pintype "passive"))
      (node (ref "U1") (pin "18") (pinfunction "SRB2_18") (pintype "bidirectional"))
    )
    (net (code "142") (name "SRB2_1") (class "Default")
      (node (ref "CA10") (pin "6") (pinfunction "6_6") (pintype "passive"))
      (node (ref "R14") (pin "6") (pinfunction "6_6") (pintype "passive"))
      (node (ref "U2") (pin "18") (pinfunction "SRB2_18") (pintype "bidirectional"))
    )
    (net (code "143") (name "SRB2_OUT") (class "Default")
      (node (ref "J22") (pin "PWR") (pinfunction "PWR_PWR") (pintype "bidirectional"))
      (node (ref "R45") (pin "3") (pinfunction "3_3") (pintype "passive"))
      (node (ref "U10") (pin "2") (pinfunction "IO2_2") (pintype "bidirectional"))
    )
    (net (code "144") (name "SRB2_OUT_1") (class "Default")
      (node (ref "J24") (pin "PWR") (pinfunction "PWR_PWR") (pintype "bidirectional"))
      (node (ref "R14") (pin "3") (pinfunction "3_3") (pintype "passive"))
      (node (ref "U16") (pin "2") (pinfunction "IO2_2") (pintype "bidirectional"))
    )
    (net (code "145") (name "START_ADS") (class "Default")
      (node (ref "A1") (pin "P$16") (pinfunction "P16_P$16") (pintype "passive"))
      (node (ref "JP3") (pin "16") (pinfunction "16_16") (pintype "passive"))
      (node (ref "U1") (pin "38") (pinfunction "START_38") (pintype "input"))
      (node (ref "U2") (pin "38") (pinfunction "START_38") (pintype "input"))
    )
    (net (code "146") (name "VREFP") (class "Default")
      (node (ref "C23") (pin "1") (pinfunction "1_1") (pintype "passive"))
      (node (ref "C24") (pin "1") (pinfunction "1_1") (pintype "passive"))
      (node (ref "JP5") (pin "2") (pinfunction "2_2") (pintype "passive"))
      (node (ref "U1") (pin "24") (pinfunction "VREFP_24") (pintype "bidirectional"))
    )
    (net (code "147") (name "VREFP_1") (class "Default")
      (node (ref "C35") (pin "1") (pinfunction "1_1") (pintype "passive"))
      (node (ref "C36") (pin "1") (pinfunction "1_1") (pintype "passive"))
      (node (ref "JP5") (pin "1") (pinfunction "1_1") (pintype "passive"))
      (node (ref "U2") (pin "24") (pinfunction "VREFP_24") (pintype "bidirectional"))
    )
    (net (code "148") (name "unconnected-(J1-Pad1)") (class "Default")
      (node (ref "J1") (pin "1") (pinfunction "1_1") (pintype "no_connect"))
    )
    (net (code "149") (name "unconnected-(J1-Pad8)") (class "Default")
      (node (ref "J1") (pin "8") (pinfunction "8_8") (pintype "no_connect"))
    )
    (net (code "150") (name "unconnected-(J1-Pad9)") (class "Default")
      (node (ref "J1") (pin "9") (pinfunction "9_9") (pintype "no_connect"))
    )
    (net (code "151") (name "unconnected-(J1-Pad10)") (class "Default")
      (node (ref "J1") (pin "10") (pinfunction "10_10") (pintype "no_connect"))
    )
    (net (code "152") (name "unconnected-(SW1-Pad2)") (class "Default")
      (node (ref "SW1") (pin "2") (pinfunction "2_2") (pintype "passive"))
    )
    (net (code "153") (name "unconnected-(U1-GPIO1-Pad42)") (class "Default")
      (node (ref "U1") (pin "42") (pinfunction "GPIO1_42") (pintype "no_connect"))
    )
    (net (code "154") (name "unconnected-(U1-GPIO2-Pad44)") (class "Default")
      (node (ref "U1") (pin "44") (pinfunction "GPIO2_44") (pintype "no_connect"))
    )
    (net (code "155") (name "unconnected-(U1-GPIO3-Pad45)") (class "Default")
      (node (ref "U1") (pin "45") (pinfunction "GPIO3_45") (pintype "no_connect"))
    )
    (net (code "156") (name "unconnected-(U1-GPIO4-Pad46)") (class "Default")
      (node (ref "U1") (pin "46") (pinfunction "GPIO4_46") (pintype "no_connect"))
    )
    (net (code "157") (name "unconnected-(U1-NC-Pad29)") (class "Default")
      (node (ref "U1") (pin "29") (pinfunction "NC_29") (pintype "no_connect"))
    )
    (net (code "158") (name "unconnected-(U1-NC_2-Pad27)") (class "Default")
      (node (ref "U1") (pin "27") (pinfunction "NC_2_27") (pintype "no_connect"))
    )
    (net (code "159") (name "unconnected-(U2-GPIO1-Pad42)") (class "Default")
      (node (ref "U2") (pin "42") (pinfunction "GPIO1_42") (pintype "no_connect"))
    )
    (net (code "160") (name "unconnected-(U2-GPIO2-Pad44)") (class "Default")
      (node (ref "U2") (pin "44") (pinfunction "GPIO2_44") (pintype "no_connect"))
    )
    (net (code "161") (name "unconnected-(U2-GPIO3-Pad45)") (class "Default")
      (node (ref "U2") (pin "45") (pinfunction "GPIO3_45") (pintype "no_connect"))
    )
    (net (code "162") (name "unconnected-(U2-GPIO4-Pad46)") (class "Default")
      (node (ref "U2") (pin "46") (pinfunction "GPIO4_46") (pintype "no_connect"))
    )
    (net (code "163") (name "unconnected-(U2-NC-Pad29)") (class "Default")
      (node (ref "U2") (pin "29") (pinfunction "NC_29") (pintype "no_connect"))
    )
    (net (code "164") (name "unconnected-(U2-NC_2-Pad27)") (class "Default")
      (node (ref "U2") (pin "27") (pinfunction "NC_2_27") (pintype "no_connect"))
    )
    (net (code "165") (name "unconnected-(U2-~{DRDY}-Pad47)") (class "Default")
      (node (ref "U2") (pin "47") (pinfunction "~{DRDY}_47") (pintype "output"))
    )
    (net (code "166") (name "unconnected-(U3-PGOOD-Pad5)") (class "Default")
      (node (ref "U3") (pin "5") (pinfunction "PGOOD_5") (pintype "no_connect"))
    )
    (net (code "167") (name "unconnected-(U6-IO1-Pad1)") (class "Default")
      (node (ref "U6") (pin "1") (pinfunction "IO1_1") (pintype "bidirectional"))
    )
    (net (code "168") (name "unconnected-(U6-NC-Pad6)") (class "Default")
      (node (ref "U6") (pin "6") (pinfunction "NC_6") (pintype "no_connect"))
    )
    (net (code "169") (name "unconnected-(U7-NC-Pad6)") (class "Default")
      (node (ref "U7") (pin "6") (pinfunction "NC_6") (pintype "no_connect"))
    )
    (net (code "170") (name "unconnected-(U8-NC-Pad6)") (class "Default")
      (node (ref "U8") (pin "6") (pinfunction "NC_6") (pintype "no_connect"))
    )
    (net (code "171") (name "unconnected-(U9-NC-Pad6)") (class "Default")
      (node (ref "U9") (pin "6") (pinfunction "NC_6") (pintype "no_connect"))
    )
    (net (code "172") (name "unconnected-(U10-IO3-Pad4)") (class "Default")
      (node (ref "U10") (pin "4") (pinfunction "IO3_4") (pintype "bidirectional"))
    )
    (net (code "173") (name "unconnected-(U10-NC-Pad6)") (class "Default")
      (node (ref "U10") (pin "6") (pinfunction "NC_6") (pintype "no_connect"))
    )
    (net (code "174") (name "unconnected-(U11-IO4-Pad5)") (class "Default")
      (node (ref "U11") (pin "5") (pinfunction "IO4_5") (pintype "bidirectional"))
    )
    (net (code "175") (name "unconnected-(U11-NC-Pad6)") (class "Default")
      (node (ref "U11") (pin "6") (pinfunction "NC_6") (pintype "no_connect"))
    )
    (net (code "176") (name "unconnected-(U12-IO1-Pad1)") (class "Default")
      (node (ref "U12") (pin "1") (pinfunction "IO1_1") (pintype "bidirectional"))
    )
    (net (code "177") (name "unconnected-(U12-NC-Pad6)") (class "Default")
      (node (ref "U12") (pin "6") (pinfunction "NC_6") (pintype "no_connect"))
    )
    (net (code "178") (name "unconnected-(U13-NC-Pad6)") (class "Default")
      (node (ref "U13") (pin "6") (pinfunction "NC_6") (pintype "no_connect"))
    )
    (net (code "179") (name "unconnected-(U14-NC-Pad6)") (class "Default")
      (node (ref "U14") (pin "6") (pinfunction "NC_6") (pintype "no_connect"))
    )
    (net (code "180") (name "unconnected-(U15-NC-Pad6)") (class "Default")
      (node (ref "U15") (pin "6") (pinfunction "NC_6") (pintype "no_connect"))
    )
    (net (code "181") (name "unconnected-(U16-IO3-Pad4)") (class "Default")
      (node (ref "U16") (pin "4") (pinfunction "IO3_4") (pintype "bidirectional"))
    )
    (net (code "182") (name "unconnected-(U16-NC-Pad6)") (class "Default")
      (node (ref "U16") (pin "6") (pinfunction "NC_6") (pintype "no_connect"))
    )
    (net (code "183") (name "unconnected-(U17-IO4-Pad5)") (class "Default")
      (node (ref "U17") (pin "5") (pinfunction "IO4_5") (pintype "bidirectional"))
    )
    (net (code "184") (name "unconnected-(U17-NC-Pad6)") (class "Default")
      (node (ref "U17") (pin "6") (pinfunction "NC_6") (pintype "no_connect"))
    )
    (net (code "185") (name "~{CS}_ADS_0") (class "Default")
      (node (ref "A1") (pin "P$15") (pinfunction "P15_P$15") (pintype "passive"))
      (node (ref "JP3") (pin "15") (pinfunction "15_15") (pintype "passive"))
      (node (ref "U1") (pin "39") (pinfunction "~{CS}_39") (pintype "input"))
    )
    (net (code "186") (name "~{CS}_ADS_1") (class "Default")
      (node (ref "A1") (pin "P$20") (pinfunction "P20_P$20") (pintype "passive"))
      (node (ref "JP3") (pin "20") (pinfunction "20_20") (pintype "passive"))
      (node (ref "U2") (pin "39") (pinfunction "~{CS}_39") (pintype "input"))
    )
    (net (code "187") (name "~{CS}_SD") (class "Default")
      (node (ref "A1") (pin "P$14") (pinfunction "P14_P$14") (pintype "passive"))
      (node (ref "J1") (pin "2") (pinfunction "2_2") (pintype "passive"))
      (node (ref "JP3") (pin "14") (pinfunction "14_14") (pintype "passive"))
    )
    (net (code "188") (name "~{INT}") (class "Default")
      (node (ref "A1") (pin "P$8") (pinfunction "P8_P$8") (pintype "passive"))
      (node (ref "JP3") (pin "8") (pinfunction "8_8") (pintype "passive"))
      (node (ref "U1") (pin "47") (pinfunction "~{DRDY}_47") (pintype "output"))
    )
    (net (code "189") (name "~{RESET}_ADS") (class "Default")
      (node (ref "A1") (pin "P$19") (pinfunction "P19_P$19") (pintype "passive"))
      (node (ref "JP3") (pin "19") (pinfunction "19_19") (pintype "passive"))
      (node (ref "U1") (pin "36") (pinfunction "~{RESET}_36") (pintype "input"))
      (node (ref "U2") (pin "36") (pinfunction "~{RESET}_36") (pintype "input"))
    )
  )
)
